# badge.net
KiCad netlist of a schematic drawn in EAGLE
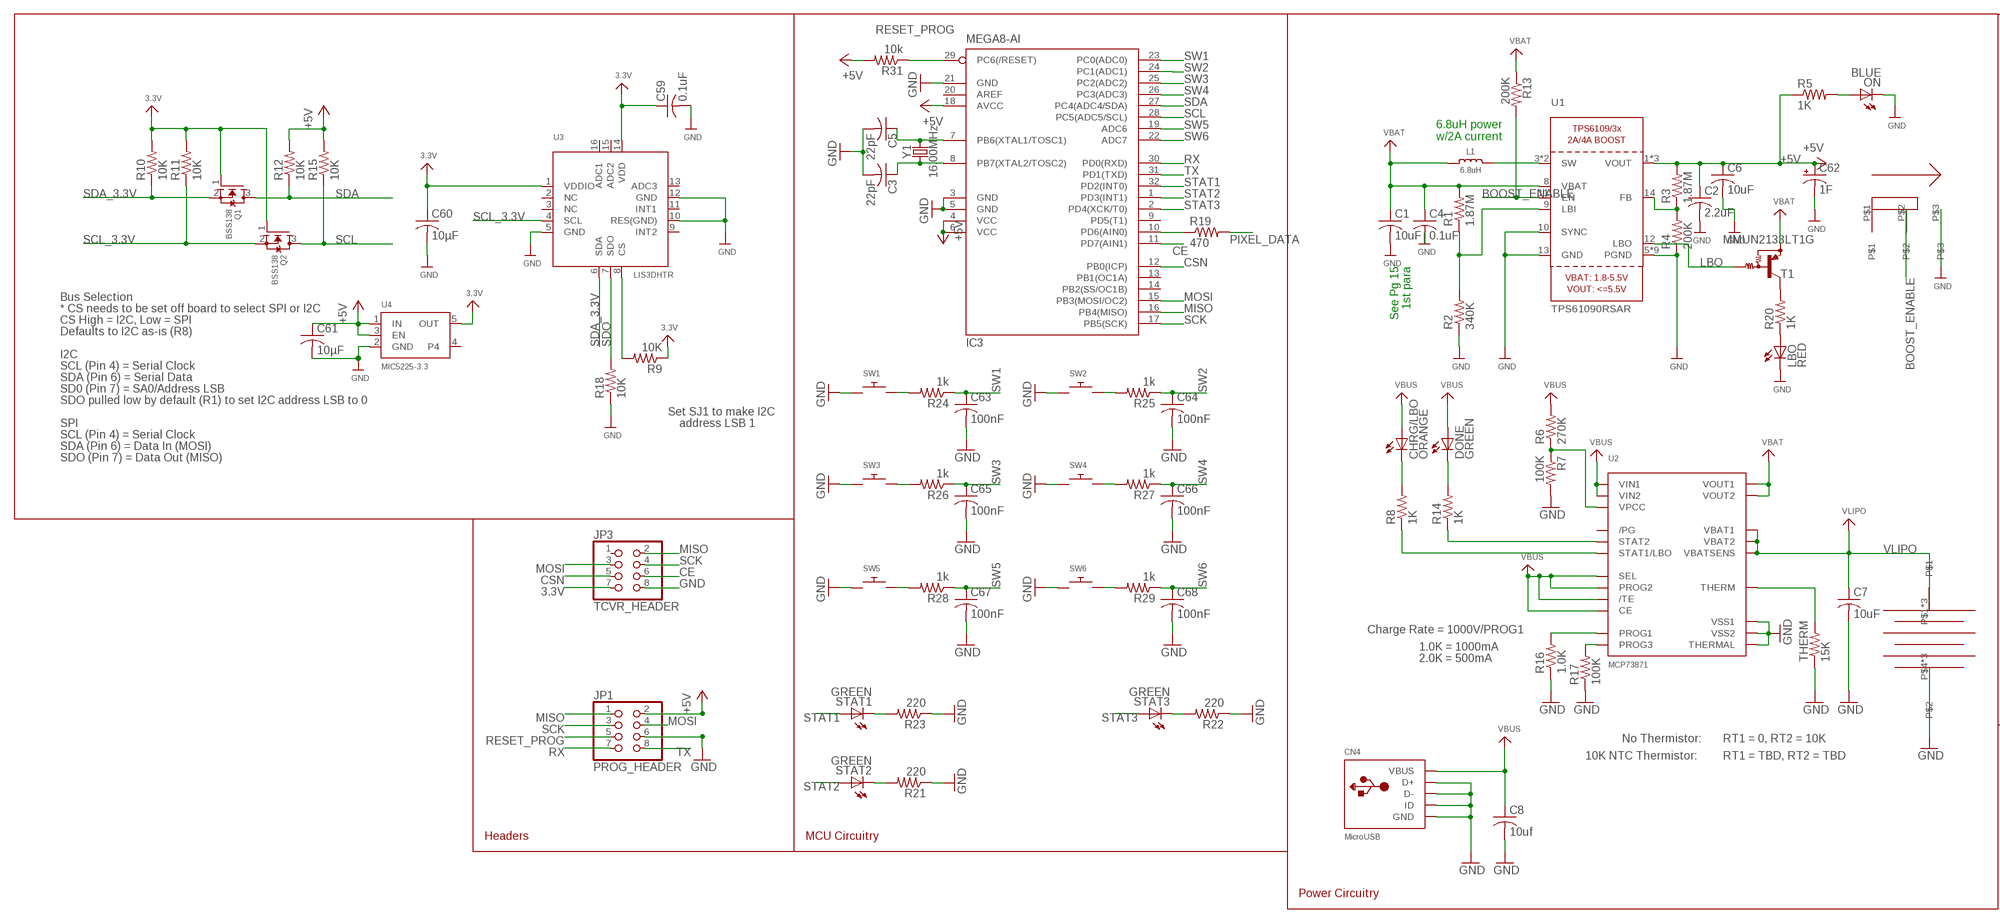
[diagram p0: schematic, sheet 1, part 1 of 2]
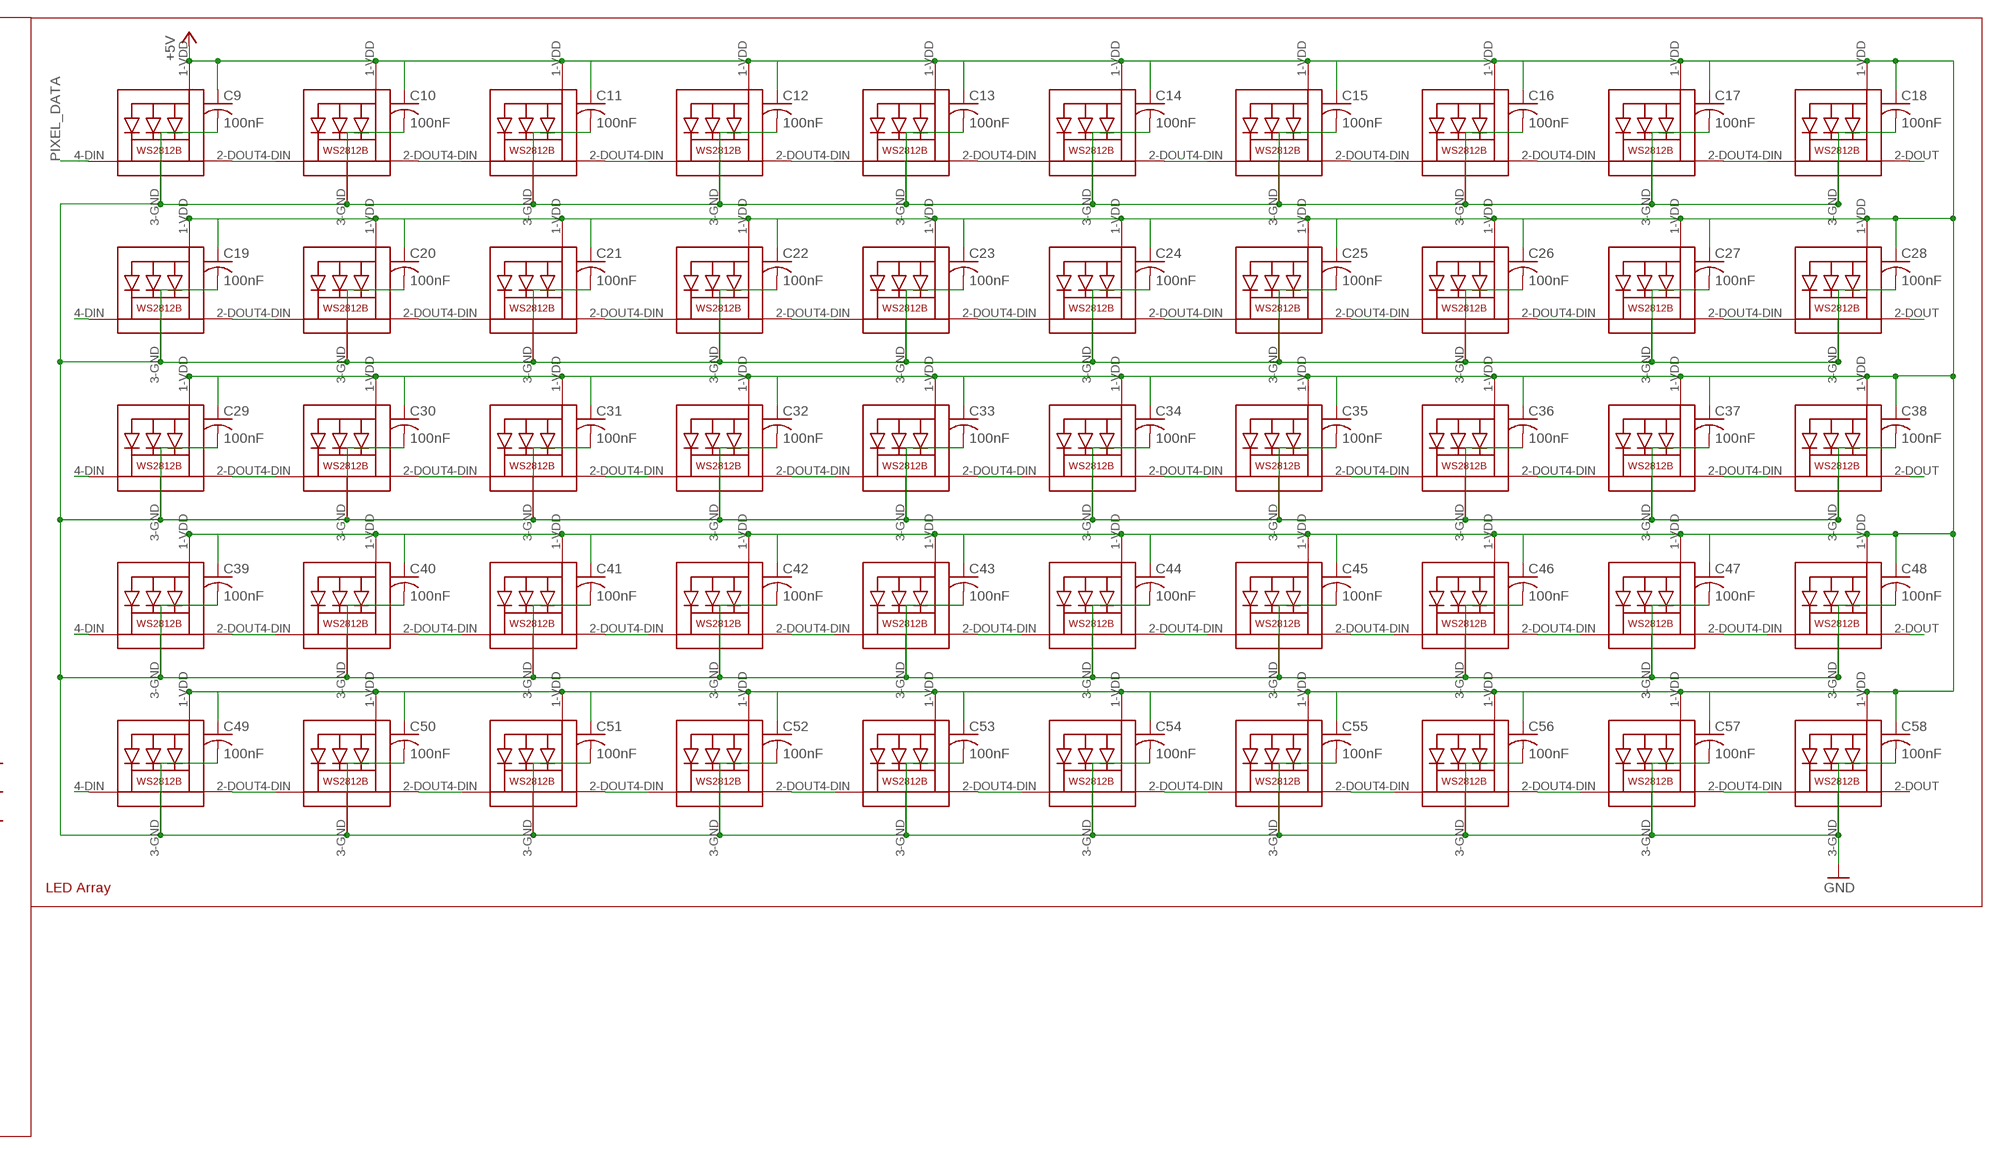
[diagram p1: schematic, sheet 1, part 2 of 2]

(export (version "E")
  (design (tool "Eeschema 10.0.6"))
  (components
    (comp (ref "C1")
      (value "10uF")
      (footprint "eagle-import:C1210")
      (libsource (lib "eagle-import") (part "resistor_348_C-USC1210"))
    )
    (comp (ref "C2")
      (value "2.2uF")
      (footprint "eagle-import:C0805")
      (libsource (lib "eagle-import") (part "C-USC0805"))
    )
    (comp (ref "C3")
      (value "22pF")
      (footprint "eagle-import:C0603")
      (libsource (lib "eagle-import") (part "resistor_348_C-USC0603"))
    )
    (comp (ref "C4")
      (value "0.1uF")
      (footprint "eagle-import:C0805")
      (libsource (lib "eagle-import") (part "C-USC0805"))
    )
    (comp (ref "C5")
      (value "22pF")
      (footprint "eagle-import:C0603")
      (libsource (lib "eagle-import") (part "resistor_348_C-USC0603"))
    )
    (comp (ref "C6")
      (value "10uF")
      (footprint "eagle-import:C1210")
      (libsource (lib "eagle-import") (part "resistor_348_C-USC1210"))
    )
    (comp (ref "C7")
      (value "10uF")
      (footprint "eagle-import:C1210")
      (libsource (lib "eagle-import") (part "resistor_348_C-USC1210"))
    )
    (comp (ref "C8")
      (value "10uf")
      (footprint "eagle-import:C0805")
      (libsource (lib "eagle-import") (part "C-USC0805"))
    )
    (comp (ref "C9")
      (value "100nF")
      (footprint "eagle-import:C0603")
      (libsource (lib "eagle-import") (part "resistor_348_C-USC0603"))
    )
    (comp (ref "C10")
      (value "100nF")
      (footprint "eagle-import:C0603")
      (libsource (lib "eagle-import") (part "resistor_348_C-USC0603"))
    )
    (comp (ref "C11")
      (value "100nF")
      (footprint "eagle-import:C0603")
      (libsource (lib "eagle-import") (part "resistor_348_C-USC0603"))
    )
    (comp (ref "C12")
      (value "100nF")
      (footprint "eagle-import:C0603")
      (libsource (lib "eagle-import") (part "resistor_348_C-USC0603"))
    )
    (comp (ref "C13")
      (value "100nF")
      (footprint "eagle-import:C0603")
      (libsource (lib "eagle-import") (part "resistor_348_C-USC0603"))
    )
    (comp (ref "C14")
      (value "100nF")
      (footprint "eagle-import:C0603")
      (libsource (lib "eagle-import") (part "resistor_348_C-USC0603"))
    )
    (comp (ref "C15")
      (value "100nF")
      (footprint "eagle-import:C0603")
      (libsource (lib "eagle-import") (part "resistor_348_C-USC0603"))
    )
    (comp (ref "C16")
      (value "100nF")
      (footprint "eagle-import:C0603")
      (libsource (lib "eagle-import") (part "resistor_348_C-USC0603"))
    )
    (comp (ref "C17")
      (value "100nF")
      (footprint "eagle-import:C0603")
      (libsource (lib "eagle-import") (part "resistor_348_C-USC0603"))
    )
    (comp (ref "C18")
      (value "100nF")
      (footprint "eagle-import:C0603")
      (libsource (lib "eagle-import") (part "resistor_348_C-USC0603"))
    )
    (comp (ref "C19")
      (value "100nF")
      (footprint "eagle-import:C0603")
      (libsource (lib "eagle-import") (part "resistor_348_C-USC0603"))
    )
    (comp (ref "C20")
      (value "100nF")
      (footprint "eagle-import:C0603")
      (libsource (lib "eagle-import") (part "resistor_348_C-USC0603"))
    )
    (comp (ref "C21")
      (value "100nF")
      (footprint "eagle-import:C0603")
      (libsource (lib "eagle-import") (part "resistor_348_C-USC0603"))
    )
    (comp (ref "C22")
      (value "100nF")
      (footprint "eagle-import:C0603")
      (libsource (lib "eagle-import") (part "resistor_348_C-USC0603"))
    )
    (comp (ref "C23")
      (value "100nF")
      (footprint "eagle-import:C0603")
      (libsource (lib "eagle-import") (part "resistor_348_C-USC0603"))
    )
    (comp (ref "C24")
      (value "100nF")
      (footprint "eagle-import:C0603")
      (libsource (lib "eagle-import") (part "resistor_348_C-USC0603"))
    )
    (comp (ref "C25")
      (value "100nF")
      (footprint "eagle-import:C0603")
      (libsource (lib "eagle-import") (part "resistor_348_C-USC0603"))
    )
    (comp (ref "C26")
      (value "100nF")
      (footprint "eagle-import:C0603")
      (libsource (lib "eagle-import") (part "resistor_348_C-USC0603"))
    )
    (comp (ref "C27")
      (value "100nF")
      (footprint "eagle-import:C0603")
      (libsource (lib "eagle-import") (part "resistor_348_C-USC0603"))
    )
    (comp (ref "C28")
      (value "100nF")
      (footprint "eagle-import:C0603")
      (libsource (lib "eagle-import") (part "resistor_348_C-USC0603"))
    )
    (comp (ref "C29")
      (value "100nF")
      (footprint "eagle-import:C0603")
      (libsource (lib "eagle-import") (part "resistor_348_C-USC0603"))
    )
    (comp (ref "C30")
      (value "100nF")
      (footprint "eagle-import:C0603")
      (libsource (lib "eagle-import") (part "resistor_348_C-USC0603"))
    )
    (comp (ref "C31")
      (value "100nF")
      (footprint "eagle-import:C0603")
      (libsource (lib "eagle-import") (part "resistor_348_C-USC0603"))
    )
    (comp (ref "C32")
      (value "100nF")
      (footprint "eagle-import:C0603")
      (libsource (lib "eagle-import") (part "resistor_348_C-USC0603"))
    )
    (comp (ref "C33")
      (value "100nF")
      (footprint "eagle-import:C0603")
      (libsource (lib "eagle-import") (part "resistor_348_C-USC0603"))
    )
    (comp (ref "C34")
      (value "100nF")
      (footprint "eagle-import:C0603")
      (libsource (lib "eagle-import") (part "resistor_348_C-USC0603"))
    )
    (comp (ref "C35")
      (value "100nF")
      (footprint "eagle-import:C0603")
      (libsource (lib "eagle-import") (part "resistor_348_C-USC0603"))
    )
    (comp (ref "C36")
      (value "100nF")
      (footprint "eagle-import:C0603")
      (libsource (lib "eagle-import") (part "resistor_348_C-USC0603"))
    )
    (comp (ref "C37")
      (value "100nF")
      (footprint "eagle-import:C0603")
      (libsource (lib "eagle-import") (part "resistor_348_C-USC0603"))
    )
    (comp (ref "C38")
      (value "100nF")
      (footprint "eagle-import:C0603")
      (libsource (lib "eagle-import") (part "resistor_348_C-USC0603"))
    )
    (comp (ref "C39")
      (value "100nF")
      (footprint "eagle-import:C0603")
      (libsource (lib "eagle-import") (part "resistor_348_C-USC0603"))
    )
    (comp (ref "C40")
      (value "100nF")
      (footprint "eagle-import:C0603")
      (libsource (lib "eagle-import") (part "resistor_348_C-USC0603"))
    )
    (comp (ref "C41")
      (value "100nF")
      (footprint "eagle-import:C0603")
      (libsource (lib "eagle-import") (part "resistor_348_C-USC0603"))
    )
    (comp (ref "C42")
      (value "100nF")
      (footprint "eagle-import:C0603")
      (libsource (lib "eagle-import") (part "resistor_348_C-USC0603"))
    )
    (comp (ref "C43")
      (value "100nF")
      (footprint "eagle-import:C0603")
      (libsource (lib "eagle-import") (part "resistor_348_C-USC0603"))
    )
    (comp (ref "C44")
      (value "100nF")
      (footprint "eagle-import:C0603")
      (libsource (lib "eagle-import") (part "resistor_348_C-USC0603"))
    )
    (comp (ref "C45")
      (value "100nF")
      (footprint "eagle-import:C0603")
      (libsource (lib "eagle-import") (part "resistor_348_C-USC0603"))
    )
    (comp (ref "C46")
      (value "100nF")
      (footprint "eagle-import:C0603")
      (libsource (lib "eagle-import") (part "resistor_348_C-USC0603"))
    )
    (comp (ref "C47")
      (value "100nF")
      (footprint "eagle-import:C0603")
      (libsource (lib "eagle-import") (part "resistor_348_C-USC0603"))
    )
    (comp (ref "C48")
      (value "100nF")
      (footprint "eagle-import:C0603")
      (libsource (lib "eagle-import") (part "resistor_348_C-USC0603"))
    )
    (comp (ref "C49")
      (value "100nF")
      (footprint "eagle-import:C0603")
      (libsource (lib "eagle-import") (part "resistor_348_C-USC0603"))
    )
    (comp (ref "C50")
      (value "100nF")
      (footprint "eagle-import:C0603")
      (libsource (lib "eagle-import") (part "resistor_348_C-USC0603"))
    )
    (comp (ref "C51")
      (value "100nF")
      (footprint "eagle-import:C0603")
      (libsource (lib "eagle-import") (part "resistor_348_C-USC0603"))
    )
    (comp (ref "C52")
      (value "100nF")
      (footprint "eagle-import:C0603")
      (libsource (lib "eagle-import") (part "resistor_348_C-USC0603"))
    )
    (comp (ref "C53")
      (value "100nF")
      (footprint "eagle-import:C0603")
      (libsource (lib "eagle-import") (part "resistor_348_C-USC0603"))
    )
    (comp (ref "C54")
      (value "100nF")
      (footprint "eagle-import:C0603")
      (libsource (lib "eagle-import") (part "resistor_348_C-USC0603"))
    )
    (comp (ref "C55")
      (value "100nF")
      (footprint "eagle-import:C0603")
      (libsource (lib "eagle-import") (part "resistor_348_C-USC0603"))
    )
    (comp (ref "C56")
      (value "100nF")
      (footprint "eagle-import:C0603")
      (libsource (lib "eagle-import") (part "resistor_348_C-USC0603"))
    )
    (comp (ref "C57")
      (value "100nF")
      (footprint "eagle-import:C0603")
      (libsource (lib "eagle-import") (part "resistor_348_C-USC0603"))
    )
    (comp (ref "C58")
      (value "100nF")
      (footprint "eagle-import:C0603")
      (libsource (lib "eagle-import") (part "resistor_348_C-USC0603"))
    )
    (comp (ref "C59")
      (value "0.1uF")
      (footprint "eagle-import:C0603")
      (libsource (lib "eagle-import") (part "resistor_348_C-USC0603"))
    )
    (comp (ref "C60")
      (value "10µF")
      (footprint "eagle-import:C0805")
      (libsource (lib "eagle-import") (part "resistor_348_C-USC0805"))
    )
    (comp (ref "C61")
      (value "10µF")
      (footprint "eagle-import:C0805")
      (libsource (lib "eagle-import") (part "resistor_348_C-USC0805"))
    )
    (comp (ref "C62")
      (value "1F")
      (footprint "eagle-import:E5-8,5")
      (libsource (lib "eagle-import") (part "CPOL-USE5-8.5"))
    )
    (comp (ref "C63")
      (value "100nF")
      (footprint "eagle-import:C0603")
      (libsource (lib "eagle-import") (part "resistor_348_C-USC0603"))
    )
    (comp (ref "C64")
      (value "100nF")
      (footprint "eagle-import:C0603")
      (libsource (lib "eagle-import") (part "resistor_348_C-USC0603"))
    )
    (comp (ref "C65")
      (value "100nF")
      (footprint "eagle-import:C0603")
      (libsource (lib "eagle-import") (part "resistor_348_C-USC0603"))
    )
    (comp (ref "C66")
      (value "100nF")
      (footprint "eagle-import:C0603")
      (libsource (lib "eagle-import") (part "resistor_348_C-USC0603"))
    )
    (comp (ref "C67")
      (value "100nF")
      (footprint "eagle-import:C0603")
      (libsource (lib "eagle-import") (part "resistor_348_C-USC0603"))
    )
    (comp (ref "C68")
      (value "100nF")
      (footprint "eagle-import:C0603")
      (libsource (lib "eagle-import") (part "resistor_348_C-USC0603"))
    )
    (comp (ref "CHRG/LBO")
      (value "ORANGE")
      (footprint "eagle-import:ADAFRUIT_CHIPLED_0603")
      (libsource (lib "eagle-import") (part "ADAFRUIT_LEDCHIPLED_0603"))
    )
    (comp (ref "CN4")
      (value "MicroUSB")
      (footprint "eagle-import:4UCONN_20329")
      (libsource (lib "eagle-import") (part "USBMICRO_20329"))
    )
    (comp (ref "DONE")
      (value "GREEN")
      (footprint "eagle-import:ADAFRUIT_CHIPLED_0603")
      (libsource (lib "eagle-import") (part "ADAFRUIT_LEDCHIPLED_0603"))
    )
    (comp (ref "IC3")
      (value "MEGA8-AI")
      (footprint "eagle-import:TQFP32-08")
      (fields (field (name "MPN") "ATMEGA8-16AU"))
      (libsource (lib "eagle-import") (part "MEGA8-AI"))
    )
    (comp (ref "JP1")
      (value "PROG_HEADER")
      (footprint "eagle-import:2X04")
      (libsource (lib "eagle-import") (part "PINHD-2X4"))
    )
    (comp (ref "JP3")
      (value "TCVR_HEADER")
      (footprint "eagle-import:2X04")
      (libsource (lib "eagle-import") (part "PINHD-2X4"))
    )
    (comp (ref "L1")
      (value "6.8uH")
      (footprint "eagle-import:INDUCTOR_5X5MM_TDK_VLC5045")
      (libsource (lib "eagle-import") (part "INDUCTORTDK_VLC5045"))
    )
    (comp (ref "LBO")
      (value "RED")
      (footprint "eagle-import:ADAFRUIT_CHIPLED_0603")
      (libsource (lib "eagle-import") (part "ADAFRUIT_LEDCHIPLED_0603"))
    )
    (comp (ref "LED1")
      (value "WS2812B5050-NARROW")
      (footprint "eagle-import:WS2812B-NARROW")
      (libsource (lib "eagle-import") (part "WS2812B5050-NARROW"))
    )
    (comp (ref "LED2")
      (value "WS2812B5050-NARROW")
      (footprint "eagle-import:WS2812B-NARROW")
      (libsource (lib "eagle-import") (part "WS2812B5050-NARROW"))
    )
    (comp (ref "LED3")
      (value "WS2812B5050-NARROW")
      (footprint "eagle-import:WS2812B-NARROW")
      (libsource (lib "eagle-import") (part "WS2812B5050-NARROW"))
    )
    (comp (ref "LED4")
      (value "WS2812B5050-NARROW")
      (footprint "eagle-import:WS2812B-NARROW")
      (libsource (lib "eagle-import") (part "WS2812B5050-NARROW"))
    )
    (comp (ref "LED5")
      (value "WS2812B5050-NARROW")
      (footprint "eagle-import:WS2812B-NARROW")
      (libsource (lib "eagle-import") (part "WS2812B5050-NARROW"))
    )
    (comp (ref "LED6")
      (value "WS2812B5050-NARROW")
      (footprint "eagle-import:WS2812B-NARROW")
      (libsource (lib "eagle-import") (part "WS2812B5050-NARROW"))
    )
    (comp (ref "LED7")
      (value "WS2812B5050-NARROW")
      (footprint "eagle-import:WS2812B-NARROW")
      (libsource (lib "eagle-import") (part "WS2812B5050-NARROW"))
    )
    (comp (ref "LED8")
      (value "WS2812B5050-NARROW")
      (footprint "eagle-import:WS2812B-NARROW")
      (libsource (lib "eagle-import") (part "WS2812B5050-NARROW"))
    )
    (comp (ref "LED9")
      (value "WS2812B5050-NARROW")
      (footprint "eagle-import:WS2812B-NARROW")
      (libsource (lib "eagle-import") (part "WS2812B5050-NARROW"))
    )
    (comp (ref "LED10")
      (value "WS2812B5050-NARROW")
      (footprint "eagle-import:WS2812B-NARROW")
      (libsource (lib "eagle-import") (part "WS2812B5050-NARROW"))
    )
    (comp (ref "LED11")
      (value "WS2812B5050-NARROW")
      (footprint "eagle-import:WS2812B-NARROW")
      (libsource (lib "eagle-import") (part "WS2812B5050-NARROW"))
    )
    (comp (ref "LED12")
      (value "WS2812B5050-NARROW")
      (footprint "eagle-import:WS2812B-NARROW")
      (libsource (lib "eagle-import") (part "WS2812B5050-NARROW"))
    )
    (comp (ref "LED13")
      (value "WS2812B5050-NARROW")
      (footprint "eagle-import:WS2812B-NARROW")
      (libsource (lib "eagle-import") (part "WS2812B5050-NARROW"))
    )
    (comp (ref "LED14")
      (value "WS2812B5050-NARROW")
      (footprint "eagle-import:WS2812B-NARROW")
      (libsource (lib "eagle-import") (part "WS2812B5050-NARROW"))
    )
    (comp (ref "LED15")
      (value "WS2812B5050-NARROW")
      (footprint "eagle-import:WS2812B-NARROW")
      (libsource (lib "eagle-import") (part "WS2812B5050-NARROW"))
    )
    (comp (ref "LED16")
      (value "WS2812B5050-NARROW")
      (footprint "eagle-import:WS2812B-NARROW")
      (libsource (lib "eagle-import") (part "WS2812B5050-NARROW"))
    )
    (comp (ref "LED17")
      (value "WS2812B5050-NARROW")
      (footprint "eagle-import:WS2812B-NARROW")
      (libsource (lib "eagle-import") (part "WS2812B5050-NARROW"))
    )
    (comp (ref "LED18")
      (value "WS2812B5050-NARROW")
      (footprint "eagle-import:WS2812B-NARROW")
      (libsource (lib "eagle-import") (part "WS2812B5050-NARROW"))
    )
    (comp (ref "LED19")
      (value "WS2812B5050-NARROW")
      (footprint "eagle-import:WS2812B-NARROW")
      (libsource (lib "eagle-import") (part "WS2812B5050-NARROW"))
    )
    (comp (ref "LED20")
      (value "WS2812B5050-NARROW")
      (footprint "eagle-import:WS2812B-NARROW")
      (libsource (lib "eagle-import") (part "WS2812B5050-NARROW"))
    )
    (comp (ref "LED21")
      (value "WS2812B5050-NARROW")
      (footprint "eagle-import:WS2812B-NARROW")
      (libsource (lib "eagle-import") (part "WS2812B5050-NARROW"))
    )
    (comp (ref "LED22")
      (value "WS2812B5050-NARROW")
      (footprint "eagle-import:WS2812B-NARROW")
      (libsource (lib "eagle-import") (part "WS2812B5050-NARROW"))
    )
    (comp (ref "LED23")
      (value "WS2812B5050-NARROW")
      (footprint "eagle-import:WS2812B-NARROW")
      (libsource (lib "eagle-import") (part "WS2812B5050-NARROW"))
    )
    (comp (ref "LED24")
      (value "WS2812B5050-NARROW")
      (footprint "eagle-import:WS2812B-NARROW")
      (libsource (lib "eagle-import") (part "WS2812B5050-NARROW"))
    )
    (comp (ref "LED25")
      (value "WS2812B5050-NARROW")
      (footprint "eagle-import:WS2812B-NARROW")
      (libsource (lib "eagle-import") (part "WS2812B5050-NARROW"))
    )
    (comp (ref "LED26")
      (value "WS2812B5050-NARROW")
      (footprint "eagle-import:WS2812B-NARROW")
      (libsource (lib "eagle-import") (part "WS2812B5050-NARROW"))
    )
    (comp (ref "LED27")
      (value "WS2812B5050-NARROW")
      (footprint "eagle-import:WS2812B-NARROW")
      (libsource (lib "eagle-import") (part "WS2812B5050-NARROW"))
    )
    (comp (ref "LED28")
      (value "WS2812B5050-NARROW")
      (footprint "eagle-import:WS2812B-NARROW")
      (libsource (lib "eagle-import") (part "WS2812B5050-NARROW"))
    )
    (comp (ref "LED29")
      (value "WS2812B5050-NARROW")
      (footprint "eagle-import:WS2812B-NARROW")
      (libsource (lib "eagle-import") (part "WS2812B5050-NARROW"))
    )
    (comp (ref "LED30")
      (value "WS2812B5050-NARROW")
      (footprint "eagle-import:WS2812B-NARROW")
      (libsource (lib "eagle-import") (part "WS2812B5050-NARROW"))
    )
    (comp (ref "LED31")
      (value "WS2812B5050-NARROW")
      (footprint "eagle-import:WS2812B-NARROW")
      (libsource (lib "eagle-import") (part "WS2812B5050-NARROW"))
    )
    (comp (ref "LED32")
      (value "WS2812B5050-NARROW")
      (footprint "eagle-import:WS2812B-NARROW")
      (libsource (lib "eagle-import") (part "WS2812B5050-NARROW"))
    )
    (comp (ref "LED33")
      (value "WS2812B5050-NARROW")
      (footprint "eagle-import:WS2812B-NARROW")
      (libsource (lib "eagle-import") (part "WS2812B5050-NARROW"))
    )
    (comp (ref "LED34")
      (value "WS2812B5050-NARROW")
      (footprint "eagle-import:WS2812B-NARROW")
      (libsource (lib "eagle-import") (part "WS2812B5050-NARROW"))
    )
    (comp (ref "LED35")
      (value "WS2812B5050-NARROW")
      (footprint "eagle-import:WS2812B-NARROW")
      (libsource (lib "eagle-import") (part "WS2812B5050-NARROW"))
    )
    (comp (ref "LED36")
      (value "WS2812B5050-NARROW")
      (footprint "eagle-import:WS2812B-NARROW")
      (libsource (lib "eagle-import") (part "WS2812B5050-NARROW"))
    )
    (comp (ref "LED37")
      (value "WS2812B5050-NARROW")
      (footprint "eagle-import:WS2812B-NARROW")
      (libsource (lib "eagle-import") (part "WS2812B5050-NARROW"))
    )
    (comp (ref "LED38")
      (value "WS2812B5050-NARROW")
      (footprint "eagle-import:WS2812B-NARROW")
      (libsource (lib "eagle-import") (part "WS2812B5050-NARROW"))
    )
    (comp (ref "LED39")
      (value "WS2812B5050-NARROW")
      (footprint "eagle-import:WS2812B-NARROW")
      (libsource (lib "eagle-import") (part "WS2812B5050-NARROW"))
    )
    (comp (ref "LED40")
      (value "WS2812B5050-NARROW")
      (footprint "eagle-import:WS2812B-NARROW")
      (libsource (lib "eagle-import") (part "WS2812B5050-NARROW"))
    )
    (comp (ref "LED41")
      (value "WS2812B5050-NARROW")
      (footprint "eagle-import:WS2812B-NARROW")
      (libsource (lib "eagle-import") (part "WS2812B5050-NARROW"))
    )
    (comp (ref "LED42")
      (value "WS2812B5050-NARROW")
      (footprint "eagle-import:WS2812B-NARROW")
      (libsource (lib "eagle-import") (part "WS2812B5050-NARROW"))
    )
    (comp (ref "LED43")
      (value "WS2812B5050-NARROW")
      (footprint "eagle-import:WS2812B-NARROW")
      (libsource (lib "eagle-import") (part "WS2812B5050-NARROW"))
    )
    (comp (ref "LED44")
      (value "WS2812B5050-NARROW")
      (footprint "eagle-import:WS2812B-NARROW")
      (libsource (lib "eagle-import") (part "WS2812B5050-NARROW"))
    )
    (comp (ref "LED45")
      (value "WS2812B5050-NARROW")
      (footprint "eagle-import:WS2812B-NARROW")
      (libsource (lib "eagle-import") (part "WS2812B5050-NARROW"))
    )
    (comp (ref "LED46")
      (value "WS2812B5050-NARROW")
      (footprint "eagle-import:WS2812B-NARROW")
      (libsource (lib "eagle-import") (part "WS2812B5050-NARROW"))
    )
    (comp (ref "LED47")
      (value "WS2812B5050-NARROW")
      (footprint "eagle-import:WS2812B-NARROW")
      (libsource (lib "eagle-import") (part "WS2812B5050-NARROW"))
    )
    (comp (ref "LED48")
      (value "WS2812B5050-NARROW")
      (footprint "eagle-import:WS2812B-NARROW")
      (libsource (lib "eagle-import") (part "WS2812B5050-NARROW"))
    )
    (comp (ref "LED49")
      (value "WS2812B5050-NARROW")
      (footprint "eagle-import:WS2812B-NARROW")
      (libsource (lib "eagle-import") (part "WS2812B5050-NARROW"))
    )
    (comp (ref "LED50")
      (value "WS2812B5050-NARROW")
      (footprint "eagle-import:WS2812B-NARROW")
      (libsource (lib "eagle-import") (part "WS2812B5050-NARROW"))
    )
    (comp (ref "ON")
      (value "BLUE")
      (footprint "eagle-import:ADAFRUIT_CHIPLED_0603")
      (libsource (lib "eagle-import") (part "ADAFRUIT_LEDCHIPLED_0603"))
    )
    (comp (ref "Q1")
      (value "BSS138")
      (footprint "eagle-import:SOT23-WIDE")
      (libsource (lib "eagle-import") (part "MOSFET-NWIDE"))
    )
    (comp (ref "Q2")
      (value "BSS138")
      (footprint "eagle-import:SOT23-WIDE")
      (libsource (lib "eagle-import") (part "MOSFET-NWIDE"))
    )
    (comp (ref "R1")
      (value "1.87M")
      (footprint "eagle-import:R0805")
      (libsource (lib "eagle-import") (part "R-US_R0805"))
    )
    (comp (ref "R2")
      (value "340K")
      (footprint "eagle-import:R0805")
      (libsource (lib "eagle-import") (part "R-US_R0805"))
    )
    (comp (ref "R3")
      (value "1.87M")
      (footprint "eagle-import:R0805")
      (libsource (lib "eagle-import") (part "R-US_R0805"))
    )
    (comp (ref "R4")
      (value "200K")
      (footprint "eagle-import:R0805")
      (libsource (lib "eagle-import") (part "R-US_R0805"))
    )
    (comp (ref "R5")
      (value "1K")
      (footprint "eagle-import:R0805")
      (libsource (lib "eagle-import") (part "R-US_R0805"))
    )
    (comp (ref "R6")
      (value "270K")
      (footprint "eagle-import:R0805")
      (libsource (lib "eagle-import") (part "R-US_R0805"))
    )
    (comp (ref "R7")
      (value "100K")
      (footprint "eagle-import:R0805")
      (libsource (lib "eagle-import") (part "R-US_R0805"))
    )
    (comp (ref "R8")
      (value "1K")
      (footprint "eagle-import:R0805")
      (libsource (lib "eagle-import") (part "R-US_R0805"))
    )
    (comp (ref "R9")
      (value "10K")
      (footprint "eagle-import:R0603")
      (libsource (lib "eagle-import") (part "resistor_348_R-US_R0603"))
    )
    (comp (ref "R10")
      (value "10K")
      (footprint "eagle-import:R0603")
      (libsource (lib "eagle-import") (part "resistor_348_R-US_R0603"))
    )
    (comp (ref "R11")
      (value "10K")
      (footprint "eagle-import:R0603")
      (libsource (lib "eagle-import") (part "resistor_348_R-US_R0603"))
    )
    (comp (ref "R12")
      (value "10K")
      (footprint "eagle-import:R0603")
      (libsource (lib "eagle-import") (part "resistor_348_R-US_R0603"))
    )
    (comp (ref "R13")
      (value "200K")
      (footprint "eagle-import:R0805")
      (libsource (lib "eagle-import") (part "R-US_R0805"))
    )
    (comp (ref "R14")
      (value "1K")
      (footprint "eagle-import:R0805")
      (libsource (lib "eagle-import") (part "R-US_R0805"))
    )
    (comp (ref "R15")
      (value "10K")
      (footprint "eagle-import:R0603")
      (libsource (lib "eagle-import") (part "resistor_348_R-US_R0603"))
    )
    (comp (ref "R16")
      (value "1.0K")
      (footprint "eagle-import:R0805")
      (libsource (lib "eagle-import") (part "R-US_R0805"))
    )
    (comp (ref "R17")
      (value "100K")
      (footprint "eagle-import:R0805")
      (libsource (lib "eagle-import") (part "R-US_R0805"))
    )
    (comp (ref "R18")
      (value "10K")
      (footprint "eagle-import:R0603")
      (libsource (lib "eagle-import") (part "resistor_348_R-US_R0603"))
    )
    (comp (ref "R19")
      (value "470")
      (footprint "eagle-import:R0805")
      (libsource (lib "eagle-import") (part "resistor_348_R-US_R0805"))
    )
    (comp (ref "R20")
      (value "1K")
      (footprint "eagle-import:R0805")
      (libsource (lib "eagle-import") (part "R-US_R0805"))
    )
    (comp (ref "R21")
      (value "220")
      (footprint "eagle-import:M0805")
      (libsource (lib "eagle-import") (part "resistor_348_R-US_M0805"))
    )
    (comp (ref "R22")
      (value "220")
      (footprint "eagle-import:M0805")
      (libsource (lib "eagle-import") (part "resistor_348_R-US_M0805"))
    )
    (comp (ref "R23")
      (value "220")
      (footprint "eagle-import:M0805")
      (libsource (lib "eagle-import") (part "resistor_348_R-US_M0805"))
    )
    (comp (ref "R24")
      (value "1k")
      (footprint "eagle-import:R0603")
      (libsource (lib "eagle-import") (part "resistor_348_R-US_R0603"))
    )
    (comp (ref "R25")
      (value "1k")
      (footprint "eagle-import:R0603")
      (libsource (lib "eagle-import") (part "resistor_348_R-US_R0603"))
    )
    (comp (ref "R26")
      (value "1k")
      (footprint "eagle-import:R0603")
      (libsource (lib "eagle-import") (part "resistor_348_R-US_R0603"))
    )
    (comp (ref "R27")
      (value "1k")
      (footprint "eagle-import:R0603")
      (libsource (lib "eagle-import") (part "resistor_348_R-US_R0603"))
    )
    (comp (ref "R28")
      (value "1k")
      (footprint "eagle-import:R0603")
      (libsource (lib "eagle-import") (part "resistor_348_R-US_R0603"))
    )
    (comp (ref "R29")
      (value "1k")
      (footprint "eagle-import:R0603")
      (libsource (lib "eagle-import") (part "resistor_348_R-US_R0603"))
    )
    (comp (ref "R31")
      (value "10k")
      (footprint "eagle-import:M0805")
      (libsource (lib "eagle-import") (part "rcl_334_R-US_M0805"))
    )
    (comp (ref "STAT1")
      (value "GREEN")
      (footprint "eagle-import:ADAFRUIT_CHIPLED_0603")
      (libsource (lib "eagle-import") (part "ADAFRUIT_LEDCHIPLED_0603"))
    )
    (comp (ref "STAT2")
      (value "GREEN")
      (footprint "eagle-import:ADAFRUIT_CHIPLED_0603")
      (libsource (lib "eagle-import") (part "ADAFRUIT_LEDCHIPLED_0603"))
    )
    (comp (ref "STAT3")
      (value "GREEN")
      (footprint "eagle-import:ADAFRUIT_CHIPLED_0603")
      (libsource (lib "eagle-import") (part "ADAFRUIT_LEDCHIPLED_0603"))
    )
    (comp (ref "SW1")
      (value "SWITCH_PUSHBUTTONEVQ-PE")
      (footprint "eagle-import:TACT_PANA-EVQ")
      (libsource (lib "eagle-import") (part "SWITCH_PUSHBUTTONEVQ-PE"))
    )
    (comp (ref "SW2")
      (value "SWITCH_PUSHBUTTONEVQ-PE")
      (footprint "eagle-import:TACT_PANA-EVQ")
      (libsource (lib "eagle-import") (part "SWITCH_PUSHBUTTONEVQ-PE"))
    )
    (comp (ref "SW3")
      (value "SWITCH_PUSHBUTTONEVQ-PE")
      (footprint "eagle-import:TACT_PANA-EVQ")
      (libsource (lib "eagle-import") (part "SWITCH_PUSHBUTTONEVQ-PE"))
    )
    (comp (ref "SW4")
      (value "SWITCH_PUSHBUTTONEVQ-PE")
      (footprint "eagle-import:TACT_PANA-EVQ")
      (libsource (lib "eagle-import") (part "SWITCH_PUSHBUTTONEVQ-PE"))
    )
    (comp (ref "SW5")
      (value "SWITCH_PUSHBUTTONEVQ-PE")
      (footprint "eagle-import:TACT_PANA-EVQ")
      (libsource (lib "eagle-import") (part "SWITCH_PUSHBUTTONEVQ-PE"))
    )
    (comp (ref "SW6")
      (value "SWITCH_PUSHBUTTONEVQ-PE")
      (footprint "eagle-import:TACT_PANA-EVQ")
      (libsource (lib "eagle-import") (part "SWITCH_PUSHBUTTONEVQ-PE"))
    )
    (comp (ref "T1")
      (value "MMUN2133LT1G")
      (footprint "eagle-import:TRANSISTOR_SC59-BEC")
      (libsource (lib "eagle-import") (part "TRANSISTOR_-PNP_DRIVER-SC59-BECMUN2113T1"))
    )
    (comp (ref "THERM")
      (value "15K")
      (footprint "eagle-import:R0805")
      (libsource (lib "eagle-import") (part "R-US_R0805"))
    )
    (comp (ref "U$17")
      (value "CL-SB-12A-02T")
      (footprint "eagle-import:CL-SB-12A-02T")
      (libsource (lib "eagle-import") (part "CL-SB-12A-02T"))
    )
    (comp (ref "U$22")
      (value "54_BATTERY_CLIP")
      (footprint "eagle-import:54_BATTERY_CLIP")
      (libsource (lib "eagle-import") (part "54_BATTERY_CLIP"))
    )
    (comp (ref "U1")
      (value "TPS61090RSAR")
      (footprint "eagle-import:PVQFN-16")
      (libsource (lib "eagle-import") (part "VREG_TPS6103X"))
    )
    (comp (ref "U2")
      (value "MCP73871")
      (footprint "eagle-import:QFN20_4MM")
      (libsource (lib "eagle-import") (part "MCP73871"))
    )
    (comp (ref "U3")
      (value "LIS3DHTR")
      (footprint "eagle-import:LGA16_3X3MM")
      (libsource (lib "eagle-import") (part "ACCEL_LIS3DHTR"))
    )
    (comp (ref "U4")
      (value "MIC5225-3.3")
      (footprint "eagle-import:SOT23-5")
      (libsource (lib "eagle-import") (part "VREG_SOT23-5"))
    )
    (comp (ref "Y1")
      (value "16.00MHz")
      (footprint "eagle-import:CRYSTAL-SMD-3.2X2.5MM")
      (libsource (lib "eagle-import") (part "CRYSTALSMD-3.2X2.5"))
    )
  )
  (nets
    (net (code "1") (name "+5V") (class "Default")
      (node (ref "C10") (pin "1") (pinfunction "1_1") (pintype "passive"))
      (node (ref "C11") (pin "1") (pinfunction "1_1") (pintype "passive"))
      (node (ref "C12") (pin "1") (pinfunction "1_1") (pintype "passive"))
      (node (ref "C13") (pin "1") (pinfunction "1_1") (pintype "passive"))
      (node (ref "C14") (pin "1") (pinfunction "1_1") (pintype "passive"))
      (node (ref "C15") (pin "1") (pinfunction "1_1") (pintype "passive"))
      (node (ref "C16") (pin "1") (pinfunction "1_1") (pintype "passive"))
      (node (ref "C17") (pin "1") (pinfunction "1_1") (pintype "passive"))
      (node (ref "C18") (pin "1") (pinfunction "1_1") (pintype "passive"))
      (node (ref "C19") (pin "1") (pinfunction "1_1") (pintype "passive"))
      (node (ref "C2") (pin "1") (pinfunction "1_1") (pintype "passive"))
      (node (ref "C20") (pin "1") (pinfunction "1_1") (pintype "passive"))
      (node (ref "C21") (pin "1") (pinfunction "1_1") (pintype "passive"))
      (node (ref "C22") (pin "1") (pinfunction "1_1") (pintype "passive"))
      (node (ref "C23") (pin "1") (pinfunction "1_1") (pintype "passive"))
      (node (ref "C24") (pin "1") (pinfunction "1_1") (pintype "passive"))
      (node (ref "C25") (pin "1") (pinfunction "1_1") (pintype "passive"))
      (node (ref "C26") (pin "1") (pinfunction "1_1") (pintype "passive"))
      (node (ref "C27") (pin "1") (pinfunction "1_1") (pintype "passive"))
      (node (ref "C28") (pin "1") (pinfunction "1_1") (pintype "passive"))
      (node (ref "C29") (pin "1") (pinfunction "1_1") (pintype "passive"))
      (node (ref "C30") (pin "1") (pinfunction "1_1") (pintype "passive"))
      (node (ref "C31") (pin "1") (pinfunction "1_1") (pintype "passive"))
      (node (ref "C32") (pin "1") (pinfunction "1_1") (pintype "passive"))
      (node (ref "C33") (pin "1") (pinfunction "1_1") (pintype "passive"))
      (node (ref "C34") (pin "1") (pinfunction "1_1") (pintype "passive"))
      (node (ref "C35") (pin "1") (pinfunction "1_1") (pintype "passive"))
      (node (ref "C36") (pin "1") (pinfunction "1_1") (pintype "passive"))
      (node (ref "C37") (pin "1") (pinfunction "1_1") (pintype "passive"))
      (node (ref "C38") (pin "1") (pinfunction "1_1") (pintype "passive"))
      (node (ref "C39") (pin "1") (pinfunction "1_1") (pintype "passive"))
      (node (ref "C40") (pin "1") (pinfunction "1_1") (pintype "passive"))
      (node (ref "C41") (pin "1") (pinfunction "1_1") (pintype "passive"))
      (node (ref "C42") (pin "1") (pinfunction "1_1") (pintype "passive"))
      (node (ref "C43") (pin "1") (pinfunction "1_1") (pintype "passive"))
      (node (ref "C44") (pin "1") (pinfunction "1_1") (pintype "passive"))
      (node (ref "C45") (pin "1") (pinfunction "1_1") (pintype "passive"))
      (node (ref "C46") (pin "1") (pinfunction "1_1") (pintype "passive"))
      (node (ref "C47") (pin "1") (pinfunction "1_1") (pintype "passive"))
      (node (ref "C48") (pin "1") (pinfunction "1_1") (pintype "passive"))
      (node (ref "C49") (pin "1") (pinfunction "1_1") (pintype "passive"))
      (node (ref "C50") (pin "1") (pinfunction "1_1") (pintype "passive"))
      (node (ref "C51") (pin "1") (pinfunction "1_1") (pintype "passive"))
      (node (ref "C52") (pin "1") (pinfunction "1_1") (pintype "passive"))
      (node (ref "C53") (pin "1") (pinfunction "1_1") (pintype "passive"))
      (node (ref "C54") (pin "1") (pinfunction "1_1") (pintype "passive"))
      (node (ref "C55") (pin "1") (pinfunction "1_1") (pintype "passive"))
      (node (ref "C56") (pin "1") (pinfunction "1_1") (pintype "passive"))
      (node (ref "C57") (pin "1") (pinfunction "1_1") (pintype "passive"))
      (node (ref "C58") (pin "1") (pinfunction "1_1") (pintype "passive"))
      (node (ref "C6") (pin "1") (pinfunction "1_1") (pintype "passive"))
      (node (ref "C61") (pin "1") (pinfunction "1_1") (pintype "passive"))
      (node (ref "C62") (pin "+") (pinfunction "+_+") (pintype "passive"))
      (node (ref "C9") (pin "1") (pinfunction "1_1") (pintype "passive"))
      (node (ref "IC3") (pin "18") (pinfunction "AVCC_18") (pintype "power_in"))
      (node (ref "IC3") (pin "4") (pinfunction "VCC_4") (pintype "power_in"))
      (node (ref "IC3") (pin "6") (pinfunction "VCC_6") (pintype "power_in"))
      (node (ref "JP1") (pin "2") (pinfunction "2_2") (pintype "passive"))
      (node (ref "LED1") (pin "1-VDD") (pinfunction "VDD_1-VDD") (pintype "power_in"))
      (node (ref "LED10") (pin "1-VDD") (pinfunction "VDD_1-VDD") (pintype "power_in"))
      (node (ref "LED11") (pin "1-VDD") (pinfunction "VDD_1-VDD") (pintype "power_in"))
      (node (ref "LED12") (pin "1-VDD") (pinfunction "VDD_1-VDD") (pintype "power_in"))
      (node (ref "LED13") (pin "1-VDD") (pinfunction "VDD_1-VDD") (pintype "power_in"))
      (node (ref "LED14") (pin "1-VDD") (pinfunction "VDD_1-VDD") (pintype "power_in"))
      (node (ref "LED15") (pin "1-VDD") (pinfunction "VDD_1-VDD") (pintype "power_in"))
      (node (ref "LED16") (pin "1-VDD") (pinfunction "VDD_1-VDD") (pintype "power_in"))
      (node (ref "LED17") (pin "1-VDD") (pinfunction "VDD_1-VDD") (pintype "power_in"))
      (node (ref "LED18") (pin "1-VDD") (pinfunction "VDD_1-VDD") (pintype "power_in"))
      (node (ref "LED19") (pin "1-VDD") (pinfunction "VDD_1-VDD") (pintype "power_in"))
      (node (ref "LED2") (pin "1-VDD") (pinfunction "VDD_1-VDD") (pintype "power_in"))
      (node (ref "LED20") (pin "1-VDD") (pinfunction "VDD_1-VDD") (pintype "power_in"))
      (node (ref "LED21") (pin "1-VDD") (pinfunction "VDD_1-VDD") (pintype "power_in"))
      (node (ref "LED22") (pin "1-VDD") (pinfunction "VDD_1-VDD") (pintype "power_in"))
      (node (ref "LED23") (pin "1-VDD") (pinfunction "VDD_1-VDD") (pintype "power_in"))
      (node (ref "LED24") (pin "1-VDD") (pinfunction "VDD_1-VDD") (pintype "power_in"))
      (node (ref "LED25") (pin "1-VDD") (pinfunction "VDD_1-VDD") (pintype "power_in"))
      (node (ref "LED26") (pin "1-VDD") (pinfunction "VDD_1-VDD") (pintype "power_in"))
      (node (ref "LED27") (pin "1-VDD") (pinfunction "VDD_1-VDD") (pintype "power_in"))
      (node (ref "LED28") (pin "1-VDD") (pinfunction "VDD_1-VDD") (pintype "power_in"))
      (node (ref "LED29") (pin "1-VDD") (pinfunction "VDD_1-VDD") (pintype "power_in"))
      (node (ref "LED3") (pin "1-VDD") (pinfunction "VDD_1-VDD") (pintype "power_in"))
      (node (ref "LED30") (pin "1-VDD") (pinfunction "VDD_1-VDD") (pintype "power_in"))
      (node (ref "LED31") (pin "1-VDD") (pinfunction "VDD_1-VDD") (pintype "power_in"))
      (node (ref "LED32") (pin "1-VDD") (pinfunction "VDD_1-VDD") (pintype "power_in"))
      (node (ref "LED33") (pin "1-VDD") (pinfunction "VDD_1-VDD") (pintype "power_in"))
      (node (ref "LED34") (pin "1-VDD") (pinfunction "VDD_1-VDD") (pintype "power_in"))
      (node (ref "LED35") (pin "1-VDD") (pinfunction "VDD_1-VDD") (pintype "power_in"))
      (node (ref "LED36") (pin "1-VDD") (pinfunction "VDD_1-VDD") (pintype "power_in"))
      (node (ref "LED37") (pin "1-VDD") (pinfunction "VDD_1-VDD") (pintype "power_in"))
      (node (ref "LED38") (pin "1-VDD") (pinfunction "VDD_1-VDD") (pintype "power_in"))
      (node (ref "LED39") (pin "1-VDD") (pinfunction "VDD_1-VDD") (pintype "power_in"))
      (node (ref "LED4") (pin "1-VDD") (pinfunction "VDD_1-VDD") (pintype "power_in"))
      (node (ref "LED40") (pin "1-VDD") (pinfunction "VDD_1-VDD") (pintype "power_in"))
      (node (ref "LED41") (pin "1-VDD") (pinfunction "VDD_1-VDD") (pintype "power_in"))
      (node (ref "LED42") (pin "1-VDD") (pinfunction "VDD_1-VDD") (pintype "power_in"))
      (node (ref "LED43") (pin "1-VDD") (pinfunction "VDD_1-VDD") (pintype "power_in"))
      (node (ref "LED44") (pin "1-VDD") (pinfunction "VDD_1-VDD") (pintype "power_in"))
      (node (ref "LED45") (pin "1-VDD") (pinfunction "VDD_1-VDD") (pintype "power_in"))
      (node (ref "LED46") (pin "1-VDD") (pinfunction "VDD_1-VDD") (pintype "power_in"))
      (node (ref "LED47") (pin "1-VDD") (pinfunction "VDD_1-VDD") (pintype "power_in"))
      (node (ref "LED48") (pin "1-VDD") (pinfunction "VDD_1-VDD") (pintype "power_in"))
      (node (ref "LED49") (pin "1-VDD") (pinfunction "VDD_1-VDD") (pintype "power_in"))
      (node (ref "LED5") (pin "1-VDD") (pinfunction "VDD_1-VDD") (pintype "power_in"))
      (node (ref "LED50") (pin "1-VDD") (pinfunction "VDD_1-VDD") (pintype "power_in"))
      (node (ref "LED6") (pin "1-VDD") (pinfunction "VDD_1-VDD") (pintype "power_in"))
      (node (ref "LED7") (pin "1-VDD") (pinfunction "VDD_1-VDD") (pintype "power_in"))
      (node (ref "LED8") (pin "1-VDD") (pinfunction "VDD_1-VDD") (pintype "power_in"))
      (node (ref "LED9") (pin "1-VDD") (pinfunction "VDD_1-VDD") (pintype "power_in"))
      (node (ref "R12") (pin "2") (pinfunction "2_2") (pintype "passive"))
      (node (ref "R15") (pin "2") (pinfunction "2_2") (pintype "passive"))
      (node (ref "R3") (pin "2") (pinfunction "2_2") (pintype "passive"))
      (node (ref "R31") (pin "2") (pinfunction "2_2") (pintype "passive"))
      (node (ref "R5") (pin "1") (pinfunction "1_1") (pintype "passive"))
      (node (ref "U1") (pin "1") (pinfunction "VOUT_1") (pintype "power_in"))
      (node (ref "U1") (pin "15") (pinfunction "VOUT_15") (pintype "power_in"))
      (node (ref "U1") (pin "16") (pinfunction "VOUT_16") (pintype "power_in"))
      (node (ref "U4") (pin "1") (pinfunction "IN_1") (pintype "power_in"))
      (node (ref "U4") (pin "3") (pinfunction "EN_3") (pintype "input"))
    )
    (net (code "2") (name "/BOOST_ENABLE") (class "Default")
      (node (ref "R13") (pin "2") (pinfunction "2_2") (pintype "passive"))
      (node (ref "U$17") (pin "P$2") (pinfunction "P$2_P$2") (pintype "bidirectional"))
      (node (ref "U1") (pin "11") (pinfunction "EN_11") (pintype "input"))
    )
    (net (code "3") (name "/CE") (class "Default")
      (node (ref "IC3") (pin "11") (pinfunction "PD7(AIN1)_11") (pintype "bidirectional"))
      (node (ref "JP3") (pin "6") (pinfunction "6_6") (pintype "passive"))
    )
    (net (code "4") (name "/CSN") (class "Default")
      (node (ref "IC3") (pin "12") (pinfunction "PB0(ICP)_12") (pintype "bidirectional"))
      (node (ref "JP3") (pin "5") (pinfunction "5_5") (pintype "passive"))
    )
    (net (code "5") (name "/LBO") (class "Default")
      (node (ref "T1") (pin "B") (pinfunction "B_B") (pintype "passive"))
      (node (ref "U1") (pin "12") (pinfunction "LBO_12") (pintype "output"))
    )
    (net (code "6") (name "/MISO") (class "Default")
      (node (ref "IC3") (pin "16") (pinfunction "PB4(MISO)_16") (pintype "bidirectional"))
      (node (ref "JP1") (pin "1") (pinfunction "1_1") (pintype "passive"))
      (node (ref "JP3") (pin "2") (pinfunction "2_2") (pintype "passive"))
    )
    (net (code "7") (name "/MOSI") (class "Default")
      (node (ref "IC3") (pin "15") (pinfunction "PB3(MOSI/OC2)_15") (pintype "bidirectional"))
      (node (ref "JP1") (pin "4") (pinfunction "4_4") (pintype "passive"))
      (node (ref "JP3") (pin "3") (pinfunction "3_3") (pintype "passive"))
    )
    (net (code "8") (name "/N$41") (class "Default")
      (node (ref "LED10") (pin "2-DOUT") (pinfunction "DO_2-DOUT") (pintype "output"))
      (node (ref "LED11") (pin "4-DIN") (pinfunction "DI_4-DIN") (pintype "input"))
    )
    (net (code "9") (name "/N$51") (class "Default")
      (node (ref "LED20") (pin "2-DOUT") (pinfunction "DO_2-DOUT") (pintype "output"))
      (node (ref "LED21") (pin "4-DIN") (pinfunction "DI_4-DIN") (pintype "input"))
    )
    (net (code "10") (name "/N$61") (class "Default")
      (node (ref "LED30") (pin "2-DOUT") (pinfunction "DO_2-DOUT") (pintype "output"))
      (node (ref "LED31") (pin "4-DIN") (pinfunction "DI_4-DIN") (pintype "input"))
    )
    (net (code "11") (name "/N$71") (class "Default")
      (node (ref "LED40") (pin "2-DOUT") (pinfunction "DO_2-DOUT") (pintype "output"))
      (node (ref "LED41") (pin "4-DIN") (pinfunction "DI_4-DIN") (pintype "input"))
    )
    (net (code "12") (name "/PIXEL_DATA") (class "Default")
      (node (ref "LED1") (pin "4-DIN") (pinfunction "DI_4-DIN") (pintype "input"))
      (node (ref "R19") (pin "2") (pinfunction "2_2") (pintype "passive"))
    )
    (net (code "13") (name "/RESET_PROG") (class "Default")
      (node (ref "IC3") (pin "29") (pinfunction "PC6(/RESET)_29") (pintype "bidirectional"))
      (node (ref "JP1") (pin "5") (pinfunction "5_5") (pintype "passive"))
      (node (ref "R31") (pin "1") (pinfunction "1_1") (pintype "passive"))
    )
    (net (code "14") (name "/RX") (class "Default")
      (node (ref "IC3") (pin "30") (pinfunction "PD0(RXD)_30") (pintype "bidirectional"))
      (node (ref "JP1") (pin "7") (pinfunction "7_7") (pintype "passive"))
    )
    (net (code "15") (name "/SCK") (class "Default")
      (node (ref "IC3") (pin "17") (pinfunction "PB5(SCK)_17") (pintype "bidirectional"))
      (node (ref "JP1") (pin "3") (pinfunction "3_3") (pintype "passive"))
      (node (ref "JP3") (pin "4") (pinfunction "4_4") (pintype "passive"))
    )
    (net (code "16") (name "/SCL") (class "Default")
      (node (ref "IC3") (pin "28") (pinfunction "PC5(ADC5/SCL)_28") (pintype "bidirectional"))
      (node (ref "Q2") (pin "3") (pinfunction "D_3") (pintype "bidirectional"))
      (node (ref "R15") (pin "1") (pinfunction "1_1") (pintype "passive"))
    )
    (net (code "17") (name "/SCL_3.3V") (class "Default")
      (node (ref "Q2") (pin "2") (pinfunction "S_2") (pintype "bidirectional"))
      (node (ref "R11") (pin "1") (pinfunction "1_1") (pintype "passive"))
      (node (ref "U3") (pin "4") (pinfunction "SCL_4") (pintype "bidirectional"))
    )
    (net (code "18") (name "/SDA") (class "Default")
      (node (ref "IC3") (pin "27") (pinfunction "PC4(ADC4/SDA)_27") (pintype "bidirectional"))
      (node (ref "Q1") (pin "3") (pinfunction "D_3") (pintype "bidirectional"))
      (node (ref "R12") (pin "1") (pinfunction "1_1") (pintype "passive"))
    )
    (net (code "19") (name "/SDA_3.3V") (class "Default")
      (node (ref "Q1") (pin "2") (pinfunction "S_2") (pintype "bidirectional"))
      (node (ref "R10") (pin "1") (pinfunction "1_1") (pintype "passive"))
      (node (ref "U3") (pin "6") (pinfunction "SDA_6") (pintype "bidirectional"))
    )
    (net (code "20") (name "/SDO") (class "Default")
      (node (ref "R18") (pin "2") (pinfunction "2_2") (pintype "passive"))
      (node (ref "U3") (pin "7") (pinfunction "SDO_7") (pintype "bidirectional"))
    )
    (net (code "21") (name "/STAT1") (class "Default")
      (node (ref "IC3") (pin "32") (pinfunction "PD2(INT0)_32") (pintype "bidirectional"))
      (node (ref "STAT1") (pin "A") (pinfunction "A_A") (pintype "passive"))
    )
    (net (code "22") (name "/STAT2") (class "Default")
      (node (ref "IC3") (pin "1") (pinfunction "PD3(INT1)_1") (pintype "bidirectional"))
      (node (ref "STAT2") (pin "A") (pinfunction "A_A") (pintype "passive"))
    )
    (net (code "23") (name "/STAT3") (class "Default")
      (node (ref "IC3") (pin "2") (pinfunction "PD4(XCK/T0)_2") (pintype "bidirectional"))
      (node (ref "STAT3") (pin "A") (pinfunction "A_A") (pintype "passive"))
    )
    (net (code "24") (name "/SW1") (class "Default")
      (node (ref "C63") (pin "1") (pinfunction "1_1") (pintype "passive"))
      (node (ref "IC3") (pin "23") (pinfunction "PC0(ADC0)_23") (pintype "bidirectional"))
      (node (ref "R24") (pin "1") (pinfunction "1_1") (pintype "passive"))
    )
    (net (code "25") (name "/SW2") (class "Default")
      (node (ref "C64") (pin "1") (pinfunction "1_1") (pintype "passive"))
      (node (ref "IC3") (pin "24") (pinfunction "PC1(ADC1)_24") (pintype "bidirectional"))
      (node (ref "R25") (pin "1") (pinfunction "1_1") (pintype "passive"))
    )
    (net (code "26") (name "/SW3") (class "Default")
      (node (ref "C65") (pin "1") (pinfunction "1_1") (pintype "passive"))
      (node (ref "IC3") (pin "25") (pinfunction "PC2(ADC2)_25") (pintype "bidirectional"))
      (node (ref "R26") (pin "1") (pinfunction "1_1") (pintype "passive"))
    )
    (net (code "27") (name "/SW4") (class "Default")
      (node (ref "C66") (pin "1") (pinfunction "1_1") (pintype "passive"))
      (node (ref "IC3") (pin "26") (pinfunction "PC3(ADC3)_26") (pintype "bidirectional"))
      (node (ref "R27") (pin "1") (pinfunction "1_1") (pintype "passive"))
    )
    (net (code "28") (name "/SW5") (class "Default")
      (node (ref "C67") (pin "1") (pinfunction "1_1") (pintype "passive"))
      (node (ref "IC3") (pin "19") (pinfunction "ADC6_19") (pintype "bidirectional"))
      (node (ref "R28") (pin "1") (pinfunction "1_1") (pintype "passive"))
    )
    (net (code "29") (name "/SW6") (class "Default")
      (node (ref "C68") (pin "1") (pinfunction "1_1") (pintype "passive"))
      (node (ref "IC3") (pin "22") (pinfunction "ADC7_22") (pintype "bidirectional"))
      (node (ref "R29") (pin "1") (pinfunction "1_1") (pintype "passive"))
    )
    (net (code "30") (name "/TX") (class "Default")
      (node (ref "IC3") (pin "31") (pinfunction "PD1(TXD)_31") (pintype "bidirectional"))
      (node (ref "JP1") (pin "8") (pinfunction "8_8") (pintype "passive"))
    )
    (net (code "31") (name "3.3V") (class "Default")
      (node (ref "C59") (pin "1") (pinfunction "1_1") (pintype "passive"))
      (node (ref "C60") (pin "1") (pinfunction "1_1") (pintype "passive"))
      (node (ref "JP3") (pin "7") (pinfunction "7_7") (pintype "passive"))
      (node (ref "Q1") (pin "1") (pinfunction "G_1") (pintype "bidirectional"))
      (node (ref "Q2") (pin "1") (pinfunction "G_1") (pintype "bidirectional"))
      (node (ref "R10") (pin "2") (pinfunction "2_2") (pintype "passive"))
      (node (ref "R11") (pin "2") (pinfunction "2_2") (pintype "passive"))
      (node (ref "R9") (pin "1") (pinfunction "1_1") (pintype "passive"))
      (node (ref "U3") (pin "1") (pinfunction "VDDIO_1") (pintype "power_in"))
      (node (ref "U3") (pin "14") (pinfunction "VDD_14") (pintype "power_in"))
      (node (ref "U4") (pin "5") (pinfunction "OUT_5") (pintype "power_in"))
    )
    (net (code "32") (name "GND") (class "Default")
      (node (ref "C1") (pin "2") (pinfunction "2_2") (pintype "passive"))
      (node (ref "C10") (pin "2") (pinfunction "2_2") (pintype "passive"))
      (node (ref "C11") (pin "2") (pinfunction "2_2") (pintype "passive"))
      (node (ref "C12") (pin "2") (pinfunction "2_2") (pintype "passive"))
      (node (ref "C13") (pin "2") (pinfunction "2_2") (pintype "passive"))
      (node (ref "C14") (pin "2") (pinfunction "2_2") (pintype "passive"))
      (node (ref "C15") (pin "2") (pinfunction "2_2") (pintype "passive"))
      (node (ref "C16") (pin "2") (pinfunction "2_2") (pintype "passive"))
      (node (ref "C17") (pin "2") (pinfunction "2_2") (pintype "passive"))
      (node (ref "C18") (pin "2") (pinfunction "2_2") (pintype "passive"))
      (node (ref "C19") (pin "2") (pinfunction "2_2") (pintype "passive"))
      (node (ref "C2") (pin "2") (pinfunction "2_2") (pintype "passive"))
      (node (ref "C20") (pin "2") (pinfunction "2_2") (pintype "passive"))
      (node (ref "C21") (pin "2") (pinfunction "2_2") (pintype "passive"))
      (node (ref "C22") (pin "2") (pinfunction "2_2") (pintype "passive"))
      (node (ref "C23") (pin "2") (pinfunction "2_2") (pintype "passive"))
      (node (ref "C24") (pin "2") (pinfunction "2_2") (pintype "passive"))
      (node (ref "C25") (pin "2") (pinfunction "2_2") (pintype "passive"))
      (node (ref "C26") (pin "2") (pinfunction "2_2") (pintype "passive"))
      (node (ref "C27") (pin "2") (pinfunction "2_2") (pintype "passive"))
      (node (ref "C28") (pin "2") (pinfunction "2_2") (pintype "passive"))
      (node (ref "C29") (pin "2") (pinfunction "2_2") (pintype "passive"))
      (node (ref "C3") (pin "2") (pinfunction "2_2") (pintype "passive"))
      (node (ref "C30") (pin "2") (pinfunction "2_2") (pintype "passive"))
      (node (ref "C31") (pin "2") (pinfunction "2_2") (pintype "passive"))
      (node (ref "C32") (pin "2") (pinfunction "2_2") (pintype "passive"))
      (node (ref "C33") (pin "2") (pinfunction "2_2") (pintype "passive"))
      (node (ref "C34") (pin "2") (pinfunction "2_2") (pintype "passive"))
      (node (ref "C35") (pin "2") (pinfunction "2_2") (pintype "passive"))
      (node (ref "C36") (pin "2") (pinfunction "2_2") (pintype "passive"))
      (node (ref "C37") (pin "2") (pinfunction "2_2") (pintype "passive"))
      (node (ref "C38") (pin "2") (pinfunction "2_2") (pintype "passive"))
      (node (ref "C39") (pin "2") (pinfunction "2_2") (pintype "passive"))
      (node (ref "C4") (pin "2") (pinfunction "2_2") (pintype "passive"))
      (node (ref "C40") (pin "2") (pinfunction "2_2") (pintype "passive"))
      (node (ref "C41") (pin "2") (pinfunction "2_2") (pintype "passive"))
      (node (ref "C42") (pin "2") (pinfunction "2_2") (pintype "passive"))
      (node (ref "C43") (pin "2") (pinfunction "2_2") (pintype "passive"))
      (node (ref "C44") (pin "2") (pinfunction "2_2") (pintype "passive"))
      (node (ref "C45") (pin "2") (pinfunction "2_2") (pintype "passive"))
      (node (ref "C46") (pin "2") (pinfunction "2_2") (pintype "passive"))
      (node (ref "C47") (pin "2") (pinfunction "2_2") (pintype "passive"))
      (node (ref "C48") (pin "2") (pinfunction "2_2") (pintype "passive"))
      (node (ref "C49") (pin "2") (pinfunction "2_2") (pintype "passive"))
      (node (ref "C5") (pin "2") (pinfunction "2_2") (pintype "passive"))
      (node (ref "C50") (pin "2") (pinfunction "2_2") (pintype "passive"))
      (node (ref "C51") (pin "2") (pinfunction "2_2") (pintype "passive"))
      (node (ref "C52") (pin "2") (pinfunction "2_2") (pintype "passive"))
      (node (ref "C53") (pin "2") (pinfunction "2_2") (pintype "passive"))
      (node (ref "C54") (pin "2") (pinfunction "2_2") (pintype "passive"))
      (node (ref "C55") (pin "2") (pinfunction "2_2") (pintype "passive"))
      (node (ref "C56") (pin "2") (pinfunction "2_2") (pintype "passive"))
      (node (ref "C57") (pin "2") (pinfunction "2_2") (pintype "passive"))
      (node (ref "C58") (pin "2") (pinfunction "2_2") (pintype "passive"))
      (node (ref "C59") (pin "2") (pinfunction "2_2") (pintype "passive"))
      (node (ref "C6") (pin "2") (pinfunction "2_2") (pintype "passive"))
      (node (ref "C60") (pin "2") (pinfunction "2_2") (pintype "passive"))
      (node (ref "C61") (pin "2") (pinfunction "2_2") (pintype "passive"))
      (node (ref "C62") (pin "-") (pinfunction "-_-") (pintype "passive"))
      (node (ref "C63") (pin "2") (pinfunction "2_2") (pintype "passive"))
      (node (ref "C64") (pin "2") (pinfunction "2_2") (pintype "passive"))
      (node (ref "C65") (pin "2") (pinfunction "2_2") (pintype "passive"))
      (node (ref "C66") (pin "2") (pinfunction "2_2") (pintype "passive"))
      (node (ref "C67") (pin "2") (pinfunction "2_2") (pintype "passive"))
      (node (ref "C68") (pin "2") (pinfunction "2_2") (pintype "passive"))
      (node (ref "C7") (pin "2") (pinfunction "2_2") (pintype "passive"))
      (node (ref "C8") (pin "2") (pinfunction "2_2") (pintype "passive"))
      (node (ref "C9") (pin "2") (pinfunction "2_2") (pintype "passive"))
      (node (ref "CN4") (pin "BASE@1") (pinfunction "GND_BASE@1") (pintype "power_in"))
      (node (ref "CN4") (pin "BASE@2") (pinfunction "GND_BASE@2") (pintype "power_in"))
      (node (ref "CN4") (pin "D+") (pinfunction "D+_D+") (pintype "bidirectional"))
      (node (ref "CN4") (pin "D-") (pinfunction "D-_D-") (pintype "bidirectional"))
      (node (ref "CN4") (pin "GND") (pinfunction "GND_GND") (pintype "power_in"))
      (node (ref "CN4") (pin "ID") (pinfunction "ID_ID") (pintype "bidirectional"))
      (node (ref "CN4") (pin "SPRT@1") (pinfunction "GND_SPRT@1") (pintype "power_in"))
      (node (ref "CN4") (pin "SPRT@2") (pinfunction "GND_SPRT@2") (pintype "power_in"))
      (node (ref "CN4") (pin "SPRT@3") (pinfunction "GND_SPRT@3") (pintype "power_in"))
      (node (ref "CN4") (pin "SPRT@4") (pinfunction "GND_SPRT@4") (pintype "power_in"))
      (node (ref "IC3") (pin "21") (pinfunction "GND_21") (pintype "power_in"))
      (node (ref "IC3") (pin "3") (pinfunction "GND_3") (pintype "power_in"))
      (node (ref "IC3") (pin "5") (pinfunction "GND_5") (pintype "power_in"))
      (node (ref "JP1") (pin "6") (pinfunction "6_6") (pintype "passive"))
      (node (ref "JP3") (pin "8") (pinfunction "8_8") (pintype "passive"))
      (node (ref "LBO") (pin "C") (pinfunction "C_C") (pintype "passive"))
      (node (ref "LED1") (pin "3-GND") (pinfunction "GND_3-GND") (pintype "power_in"))
      (node (ref "LED10") (pin "3-GND") (pinfunction "GND_3-GND") (pintype "power_in"))
      (node (ref "LED11") (pin "3-GND") (pinfunction "GND_3-GND") (pintype "power_in"))
      (node (ref "LED12") (pin "3-GND") (pinfunction "GND_3-GND") (pintype "power_in"))
      (node (ref "LED13") (pin "3-GND") (pinfunction "GND_3-GND") (pintype "power_in"))
      (node (ref "LED14") (pin "3-GND") (pinfunction "GND_3-GND") (pintype "power_in"))
      (node (ref "LED15") (pin "3-GND") (pinfunction "GND_3-GND") (pintype "power_in"))
      (node (ref "LED16") (pin "3-GND") (pinfunction "GND_3-GND") (pintype "power_in"))
      (node (ref "LED17") (pin "3-GND") (pinfunction "GND_3-GND") (pintype "power_in"))
      (node (ref "LED18") (pin "3-GND") (pinfunction "GND_3-GND") (pintype "power_in"))
      (node (ref "LED19") (pin "3-GND") (pinfunction "GND_3-GND") (pintype "power_in"))
      (node (ref "LED2") (pin "3-GND") (pinfunction "GND_3-GND") (pintype "power_in"))
      (node (ref "LED20") (pin "3-GND") (pinfunction "GND_3-GND") (pintype "power_in"))
      (node (ref "LED21") (pin "3-GND") (pinfunction "GND_3-GND") (pintype "power_in"))
      (node (ref "LED22") (pin "3-GND") (pinfunction "GND_3-GND") (pintype "power_in"))
      (node (ref "LED23") (pin "3-GND") (pinfunction "GND_3-GND") (pintype "power_in"))
      (node (ref "LED24") (pin "3-GND") (pinfunction "GND_3-GND") (pintype "power_in"))
      (node (ref "LED25") (pin "3-GND") (pinfunction "GND_3-GND") (pintype "power_in"))
      (node (ref "LED26") (pin "3-GND") (pinfunction "GND_3-GND") (pintype "power_in"))
      (node (ref "LED27") (pin "3-GND") (pinfunction "GND_3-GND") (pintype "power_in"))
      (node (ref "LED28") (pin "3-GND") (pinfunction "GND_3-GND") (pintype "power_in"))
      (node (ref "LED29") (pin "3-GND") (pinfunction "GND_3-GND") (pintype "power_in"))
      (node (ref "LED3") (pin "3-GND") (pinfunction "GND_3-GND") (pintype "power_in"))
      (node (ref "LED30") (pin "3-GND") (pinfunction "GND_3-GND") (pintype "power_in"))
      (node (ref "LED31") (pin "3-GND") (pinfunction "GND_3-GND") (pintype "power_in"))
      (node (ref "LED32") (pin "3-GND") (pinfunction "GND_3-GND") (pintype "power_in"))
      (node (ref "LED33") (pin "3-GND") (pinfunction "GND_3-GND") (pintype "power_in"))
      (node (ref "LED34") (pin "3-GND") (pinfunction "GND_3-GND") (pintype "power_in"))
      (node (ref "LED35") (pin "3-GND") (pinfunction "GND_3-GND") (pintype "power_in"))
      (node (ref "LED36") (pin "3-GND") (pinfunction "GND_3-GND") (pintype "power_in"))
      (node (ref "LED37") (pin "3-GND") (pinfunction "GND_3-GND") (pintype "power_in"))
      (node (ref "LED38") (pin "3-GND") (pinfunction "GND_3-GND") (pintype "power_in"))
      (node (ref "LED39") (pin "3-GND") (pinfunction "GND_3-GND") (pintype "power_in"))
      (node (ref "LED4") (pin "3-GND") (pinfunction "GND_3-GND") (pintype "power_in"))
      (node (ref "LED40") (pin "3-GND") (pinfunction "GND_3-GND") (pintype "power_in"))
      (node (ref "LED41") (pin "3-GND") (pinfunction "GND_3-GND") (pintype "power_in"))
      (node (ref "LED42") (pin "3-GND") (pinfunction "GND_3-GND") (pintype "power_in"))
      (node (ref "LED43") (pin "3-GND") (pinfunction "GND_3-GND") (pintype "power_in"))
      (node (ref "LED44") (pin "3-GND") (pinfunction "GND_3-GND") (pintype "power_in"))
      (node (ref "LED45") (pin "3-GND") (pinfunction "GND_3-GND") (pintype "power_in"))
      (node (ref "LED46") (pin "3-GND") (pinfunction "GND_3-GND") (pintype "power_in"))
      (node (ref "LED47") (pin "3-GND") (pinfunction "GND_3-GND") (pintype "power_in"))
      (node (ref "LED48") (pin "3-GND") (pinfunction "GND_3-GND") (pintype "power_in"))
      (node (ref "LED49") (pin "3-GND") (pinfunction "GND_3-GND") (pintype "power_in"))
      (node (ref "LED5") (pin "3-GND") (pinfunction "GND_3-GND") (pintype "power_in"))
      (node (ref "LED50") (pin "3-GND") (pinfunction "GND_3-GND") (pintype "power_in"))
      (node (ref "LED6") (pin "3-GND") (pinfunction "GND_3-GND") (pintype "power_in"))
      (node (ref "LED7") (pin "3-GND") (pinfunction "GND_3-GND") (pintype "power_in"))
      (node (ref "LED8") (pin "3-GND") (pinfunction "GND_3-GND") (pintype "power_in"))
      (node (ref "LED9") (pin "3-GND") (pinfunction "GND_3-GND") (pintype "power_in"))
      (node (ref "ON") (pin "C") (pinfunction "C_C") (pintype "passive"))
      (node (ref "R16") (pin "1") (pinfunction "1_1") (pintype "passive"))
      (node (ref "R17") (pin "1") (pinfunction "1_1") (pintype "passive"))
      (node (ref "R18") (pin "1") (pinfunction "1_1") (pintype "passive"))
      (node (ref "R2") (pin "1") (pinfunction "1_1") (pintype "passive"))
      (node (ref "R21") (pin "1") (pinfunction "1_1") (pintype "passive"))
      (node (ref "R22") (pin "1") (pinfunction "1_1") (pintype "passive"))
      (node (ref "R23") (pin "1") (pinfunction "1_1") (pintype "passive"))
      (node (ref "R4") (pin "1") (pinfunction "1_1") (pintype "passive"))
      (node (ref "R7") (pin "2") (pinfunction "2_2") (pintype "passive"))
      (node (ref "SW1") (pin "P$1") (pinfunction "P$1_P$1") (pintype "passive"))
      (node (ref "SW2") (pin "P$1") (pinfunction "P$1_P$1") (pintype "passive"))
      (node (ref "SW3") (pin "P$1") (pinfunction "P$1_P$1") (pintype "passive"))
      (node (ref "SW4") (pin "P$1") (pinfunction "P$1_P$1") (pintype "passive"))
      (node (ref "SW5") (pin "P$1") (pinfunction "P$1_P$1") (pintype "passive"))
      (node (ref "SW6") (pin "P$1") (pinfunction "P$1_P$1") (pintype "passive"))
      (node (ref "THERM") (pin "1") (pinfunction "1_1") (pintype "passive"))
      (node (ref "U$17") (pin "P$3") (pinfunction "P$3_P$3") (pintype "bidirectional"))
      (node (ref "U$22") (pin "P$4") (pinfunction "P$2_P$4") (pintype "bidirectional"))
      (node (ref "U$22") (pin "P$5") (pinfunction "P$2_P$5") (pintype "bidirectional"))
      (node (ref "U$22") (pin "P$6") (pinfunction "P$2_P$6") (pintype "bidirectional"))
      (node (ref "U1") (pin "10") (pinfunction "SYNC_10") (pintype "input"))
      (node (ref "U1") (pin "13") (pinfunction "GND_13") (pintype "power_in"))
      (node (ref "U1") (pin "5") (pinfunction "PGND_5") (pintype "power_in"))
      (node (ref "U1") (pin "6") (pinfunction "PGND_6") (pintype "power_in"))
      (node (ref "U1") (pin "7") (pinfunction "PGND_7") (pintype "power_in"))
      (node (ref "U1") (pin "P$18") (pinfunction "PGND_P$18") (pintype "power_in"))
      (node (ref "U1") (pin "P$19") (pinfunction "PGND_P$19") (pintype "power_in"))
      (node (ref "U1") (pin "P$20") (pinfunction "PGND_P$20") (pintype "power_in"))
      (node (ref "U1") (pin "P$21") (pinfunction "PGND_P$21") (pintype "power_in"))
      (node (ref "U1") (pin "P$22") (pinfunction "PGND_P$22") (pintype "power_in"))
      (node (ref "U1") (pin "THERMAL") (pinfunction "PGND_THERMAL") (pintype "power_in"))
      (node (ref "U2") (pin "P$10") (pinfunction "VSS1_P$10") (pintype "bidirectional"))
      (node (ref "U2") (pin "P$11") (pinfunction "VSS2_P$11") (pintype "bidirectional"))
      (node (ref "U2") (pin "P$21") (pinfunction "THERMAL_P$21") (pintype "bidirectional"))
      (node (ref "U3") (pin "10") (pinfunction "RES(GND)_10") (pintype "bidirectional"))
      (node (ref "U3") (pin "12") (pinfunction "GND_12") (pintype "power_in"))
      (node (ref "U3") (pin "5") (pinfunction "GND_5") (pintype "power_in"))
      (node (ref "U4") (pin "2") (pinfunction "GND_2") (pintype "power_in"))
    )
    (net (code "33") (name "Net-(CHRG/LBO-PadC)") (class "Default")
      (node (ref "CHRG/LBO") (pin "C") (pinfunction "C_C") (pintype "passive"))
      (node (ref "R8") (pin "2") (pinfunction "2_2") (pintype "passive"))
    )
    (net (code "34") (name "Net-(DONE-PadC)") (class "Default")
      (node (ref "DONE") (pin "C") (pinfunction "C_C") (pintype "passive"))
      (node (ref "R14") (pin "2") (pinfunction "2_2") (pintype "passive"))
    )
    (net (code "35") (name "Net-(IC3-PB6(XTAL1{slash}TOSC1))") (class "Default")
      (node (ref "C5") (pin "1") (pinfunction "1_1") (pintype "passive"))
      (node (ref "IC3") (pin "7") (pinfunction "PB6(XTAL1/TOSC1)_7") (pintype "bidirectional"))
      (node (ref "Y1") (pin "3") (pinfunction "2_3") (pintype "passive"))
    )
    (net (code "36") (name "Net-(IC3-PB7(XTAL2{slash}TOSC2))") (class "Default")
      (node (ref "C3") (pin "1") (pinfunction "1_1") (pintype "passive"))
      (node (ref "IC3") (pin "8") (pinfunction "PB7(XTAL2/TOSC2)_8") (pintype "bidirectional"))
      (node (ref "Y1") (pin "1") (pinfunction "1_1") (pintype "passive"))
    )
    (net (code "37") (name "Net-(IC3-PD6(AIN0))") (class "Default")
      (node (ref "IC3") (pin "10") (pinfunction "PD6(AIN0)_10") (pintype "bidirectional"))
      (node (ref "R19") (pin "1") (pinfunction "1_1") (pintype "passive"))
    )
    (net (code "38") (name "Net-(L1-2)") (class "Default")
      (node (ref "L1") (pin "P$2") (pinfunction "2_P$2") (pintype "passive"))
      (node (ref "U1") (pin "3") (pinfunction "SW_3") (pintype "input"))
      (node (ref "U1") (pin "4") (pinfunction "SW_4") (pintype "input"))
    )
    (net (code "39") (name "Net-(LBO-PadA)") (class "Default")
      (node (ref "LBO") (pin "A") (pinfunction "A_A") (pintype "passive"))
      (node (ref "R20") (pin "1") (pinfunction "1_1") (pintype "passive"))
    )
    (net (code "40") (name "Net-(LED1-DO)") (class "Default")
      (node (ref "LED1") (pin "2-DOUT") (pinfunction "DO_2-DOUT") (pintype "output"))
      (node (ref "LED2") (pin "4-DIN") (pinfunction "DI_4-DIN") (pintype "input"))
    )
    (net (code "41") (name "Net-(LED2-DO)") (class "Default")
      (node (ref "LED2") (pin "2-DOUT") (pinfunction "DO_2-DOUT") (pintype "output"))
      (node (ref "LED3") (pin "4-DIN") (pinfunction "DI_4-DIN") (pintype "input"))
    )
    (net (code "42") (name "Net-(LED3-DO)") (class "Default")
      (node (ref "LED3") (pin "2-DOUT") (pinfunction "DO_2-DOUT") (pintype "output"))
      (node (ref "LED4") (pin "4-DIN") (pinfunction "DI_4-DIN") (pintype "input"))
    )
    (net (code "43") (name "Net-(LED4-DO)") (class "Default")
      (node (ref "LED4") (pin "2-DOUT") (pinfunction "DO_2-DOUT") (pintype "output"))
      (node (ref "LED5") (pin "4-DIN") (pinfunction "DI_4-DIN") (pintype "input"))
    )
    (net (code "44") (name "Net-(LED5-DO)") (class "Default")
      (node (ref "LED5") (pin "2-DOUT") (pinfunction "DO_2-DOUT") (pintype "output"))
      (node (ref "LED6") (pin "4-DIN") (pinfunction "DI_4-DIN") (pintype "input"))
    )
    (net (code "45") (name "Net-(LED6-DO)") (class "Default")
      (node (ref "LED6") (pin "2-DOUT") (pinfunction "DO_2-DOUT") (pintype "output"))
      (node (ref "LED7") (pin "4-DIN") (pinfunction "DI_4-DIN") (pintype "input"))
    )
    (net (code "46") (name "Net-(LED7-DO)") (class "Default")
      (node (ref "LED7") (pin "2-DOUT") (pinfunction "DO_2-DOUT") (pintype "output"))
      (node (ref "LED8") (pin "4-DIN") (pinfunction "DI_4-DIN") (pintype "input"))
    )
    (net (code "47") (name "Net-(LED8-DO)") (class "Default")
      (node (ref "LED8") (pin "2-DOUT") (pinfunction "DO_2-DOUT") (pintype "output"))
      (node (ref "LED9") (pin "4-DIN") (pinfunction "DI_4-DIN") (pintype "input"))
    )
    (net (code "48") (name "Net-(LED10-DI)") (class "Default")
      (node (ref "LED10") (pin "4-DIN") (pinfunction "DI_4-DIN") (pintype "input"))
      (node (ref "LED9") (pin "2-DOUT") (pinfunction "DO_2-DOUT") (pintype "output"))
    )
    (net (code "49") (name "Net-(LED11-DO)") (class "Default")
      (node (ref "LED11") (pin "2-DOUT") (pinfunction "DO_2-DOUT") (pintype "output"))
      (node (ref "LED12") (pin "4-DIN") (pinfunction "DI_4-DIN") (pintype "input"))
    )
    (net (code "50") (name "Net-(LED12-DO)") (class "Default")
      (node (ref "LED12") (pin "2-DOUT") (pinfunction "DO_2-DOUT") (pintype "output"))
      (node (ref "LED13") (pin "4-DIN") (pinfunction "DI_4-DIN") (pintype "input"))
    )
    (net (code "51") (name "Net-(LED13-DO)") (class "Default")
      (node (ref "LED13") (pin "2-DOUT") (pinfunction "DO_2-DOUT") (pintype "output"))
      (node (ref "LED14") (pin "4-DIN") (pinfunction "DI_4-DIN") (pintype "input"))
    )
    (net (code "52") (name "Net-(LED14-DO)") (class "Default")
      (node (ref "LED14") (pin "2-DOUT") (pinfunction "DO_2-DOUT") (pintype "output"))
      (node (ref "LED15") (pin "4-DIN") (pinfunction "DI_4-DIN") (pintype "input"))
    )
    (net (code "53") (name "Net-(LED15-DO)") (class "Default")
      (node (ref "LED15") (pin "2-DOUT") (pinfunction "DO_2-DOUT") (pintype "output"))
      (node (ref "LED16") (pin "4-DIN") (pinfunction "DI_4-DIN") (pintype "input"))
    )
    (net (code "54") (name "Net-(LED16-DO)") (class "Default")
      (node (ref "LED16") (pin "2-DOUT") (pinfunction "DO_2-DOUT") (pintype "output"))
      (node (ref "LED17") (pin "4-DIN") (pinfunction "DI_4-DIN") (pintype "input"))
    )
    (net (code "55") (name "Net-(LED17-DO)") (class "Default")
      (node (ref "LED17") (pin "2-DOUT") (pinfunction "DO_2-DOUT") (pintype "output"))
      (node (ref "LED18") (pin "4-DIN") (pinfunction "DI_4-DIN") (pintype "input"))
    )
    (net (code "56") (name "Net-(LED18-DO)") (class "Default")
      (node (ref "LED18") (pin "2-DOUT") (pinfunction "DO_2-DOUT") (pintype "output"))
      (node (ref "LED19") (pin "4-DIN") (pinfunction "DI_4-DIN") (pintype "input"))
    )
    (net (code "57") (name "Net-(LED19-DO)") (class "Default")
      (node (ref "LED19") (pin "2-DOUT") (pinfunction "DO_2-DOUT") (pintype "output"))
      (node (ref "LED20") (pin "4-DIN") (pinfunction "DI_4-DIN") (pintype "input"))
    )
    (net (code "58") (name "Net-(LED21-DO)") (class "Default")
      (node (ref "LED21") (pin "2-DOUT") (pinfunction "DO_2-DOUT") (pintype "output"))
      (node (ref "LED22") (pin "4-DIN") (pinfunction "DI_4-DIN") (pintype "input"))
    )
    (net (code "59") (name "Net-(LED22-DO)") (class "Default")
      (node (ref "LED22") (pin "2-DOUT") (pinfunction "DO_2-DOUT") (pintype "output"))
      (node (ref "LED23") (pin "4-DIN") (pinfunction "DI_4-DIN") (pintype "input"))
    )
    (net (code "60") (name "Net-(LED23-DO)") (class "Default")
      (node (ref "LED23") (pin "2-DOUT") (pinfunction "DO_2-DOUT") (pintype "output"))
      (node (ref "LED24") (pin "4-DIN") (pinfunction "DI_4-DIN") (pintype "input"))
    )
    (net (code "61") (name "Net-(LED24-DO)") (class "Default")
      (node (ref "LED24") (pin "2-DOUT") (pinfunction "DO_2-DOUT") (pintype "output"))
      (node (ref "LED25") (pin "4-DIN") (pinfunction "DI_4-DIN") (pintype "input"))
    )
    (net (code "62") (name "Net-(LED25-DO)") (class "Default")
      (node (ref "LED25") (pin "2-DOUT") (pinfunction "DO_2-DOUT") (pintype "output"))
      (node (ref "LED26") (pin "4-DIN") (pinfunction "DI_4-DIN") (pintype "input"))
    )
    (net (code "63") (name "Net-(LED26-DO)") (class "Default")
      (node (ref "LED26") (pin "2-DOUT") (pinfunction "DO_2-DOUT") (pintype "output"))
      (node (ref "LED27") (pin "4-DIN") (pinfunction "DI_4-DIN") (pintype "input"))
    )
    (net (code "64") (name "Net-(LED27-DO)") (class "Default")
      (node (ref "LED27") (pin "2-DOUT") (pinfunction "DO_2-DOUT") (pintype "output"))
      (node (ref "LED28") (pin "4-DIN") (pinfunction "DI_4-DIN") (pintype "input"))
    )
    (net (code "65") (name "Net-(LED28-DO)") (class "Default")
      (node (ref "LED28") (pin "2-DOUT") (pinfunction "DO_2-DOUT") (pintype "output"))
      (node (ref "LED29") (pin "4-DIN") (pinfunction "DI_4-DIN") (pintype "input"))
    )
    (net (code "66") (name "Net-(LED29-DO)") (class "Default")
      (node (ref "LED29") (pin "2-DOUT") (pinfunction "DO_2-DOUT") (pintype "output"))
      (node (ref "LED30") (pin "4-DIN") (pinfunction "DI_4-DIN") (pintype "input"))
    )
    (net (code "67") (name "Net-(LED31-DO)") (class "Default")
      (node (ref "LED31") (pin "2-DOUT") (pinfunction "DO_2-DOUT") (pintype "output"))
      (node (ref "LED32") (pin "4-DIN") (pinfunction "DI_4-DIN") (pintype "input"))
    )
    (net (code "68") (name "Net-(LED32-DO)") (class "Default")
      (node (ref "LED32") (pin "2-DOUT") (pinfunction "DO_2-DOUT") (pintype "output"))
      (node (ref "LED33") (pin "4-DIN") (pinfunction "DI_4-DIN") (pintype "input"))
    )
    (net (code "69") (name "Net-(LED33-DO)") (class "Default")
      (node (ref "LED33") (pin "2-DOUT") (pinfunction "DO_2-DOUT") (pintype "output"))
      (node (ref "LED34") (pin "4-DIN") (pinfunction "DI_4-DIN") (pintype "input"))
    )
    (net (code "70") (name "Net-(LED34-DO)") (class "Default")
      (node (ref "LED34") (pin "2-DOUT") (pinfunction "DO_2-DOUT") (pintype "output"))
      (node (ref "LED35") (pin "4-DIN") (pinfunction "DI_4-DIN") (pintype "input"))
    )
    (net (code "71") (name "Net-(LED35-DO)") (class "Default")
      (node (ref "LED35") (pin "2-DOUT") (pinfunction "DO_2-DOUT") (pintype "output"))
      (node (ref "LED36") (pin "4-DIN") (pinfunction "DI_4-DIN") (pintype "input"))
    )
    (net (code "72") (name "Net-(LED36-DO)") (class "Default")
      (node (ref "LED36") (pin "2-DOUT") (pinfunction "DO_2-DOUT") (pintype "output"))
      (node (ref "LED37") (pin "4-DIN") (pinfunction "DI_4-DIN") (pintype "input"))
    )
    (net (code "73") (name "Net-(LED37-DO)") (class "Default")
      (node (ref "LED37") (pin "2-DOUT") (pinfunction "DO_2-DOUT") (pintype "output"))
      (node (ref "LED38") (pin "4-DIN") (pinfunction "DI_4-DIN") (pintype "input"))
    )
    (net (code "74") (name "Net-(LED38-DO)") (class "Default")
      (node (ref "LED38") (pin "2-DOUT") (pinfunction "DO_2-DOUT") (pintype "output"))
      (node (ref "LED39") (pin "4-DIN") (pinfunction "DI_4-DIN") (pintype "input"))
    )
    (net (code "75") (name "Net-(LED39-DO)") (class "Default")
      (node (ref "LED39") (pin "2-DOUT") (pinfunction "DO_2-DOUT") (pintype "output"))
      (node (ref "LED40") (pin "4-DIN") (pinfunction "DI_4-DIN") (pintype "input"))
    )
    (net (code "76") (name "Net-(LED41-DO)") (class "Default")
      (node (ref "LED41") (pin "2-DOUT") (pinfunction "DO_2-DOUT") (pintype "output"))
      (node (ref "LED42") (pin "4-DIN") (pinfunction "DI_4-DIN") (pintype "input"))
    )
    (net (code "77") (name "Net-(LED42-DO)") (class "Default")
      (node (ref "LED42") (pin "2-DOUT") (pinfunction "DO_2-DOUT") (pintype "output"))
      (node (ref "LED43") (pin "4-DIN") (pinfunction "DI_4-DIN") (pintype "input"))
    )
    (net (code "78") (name "Net-(LED43-DO)") (class "Default")
      (node (ref "LED43") (pin "2-DOUT") (pinfunction "DO_2-DOUT") (pintype "output"))
      (node (ref "LED44") (pin "4-DIN") (pinfunction "DI_4-DIN") (pintype "input"))
    )
    (net (code "79") (name "Net-(LED44-DO)") (class "Default")
      (node (ref "LED44") (pin "2-DOUT") (pinfunction "DO_2-DOUT") (pintype "output"))
      (node (ref "LED45") (pin "4-DIN") (pinfunction "DI_4-DIN") (pintype "input"))
    )
    (net (code "80") (name "Net-(LED45-DO)") (class "Default")
      (node (ref "LED45") (pin "2-DOUT") (pinfunction "DO_2-DOUT") (pintype "output"))
      (node (ref "LED46") (pin "4-DIN") (pinfunction "DI_4-DIN") (pintype "input"))
    )
    (net (code "81") (name "Net-(LED46-DO)") (class "Default")
      (node (ref "LED46") (pin "2-DOUT") (pinfunction "DO_2-DOUT") (pintype "output"))
      (node (ref "LED47") (pin "4-DIN") (pinfunction "DI_4-DIN") (pintype "input"))
    )
    (net (code "82") (name "Net-(LED47-DO)") (class "Default")
      (node (ref "LED47") (pin "2-DOUT") (pinfunction "DO_2-DOUT") (pintype "output"))
      (node (ref "LED48") (pin "4-DIN") (pinfunction "DI_4-DIN") (pintype "input"))
    )
    (net (code "83") (name "Net-(LED48-DO)") (class "Default")
      (node (ref "LED48") (pin "2-DOUT") (pinfunction "DO_2-DOUT") (pintype "output"))
      (node (ref "LED49") (pin "4-DIN") (pinfunction "DI_4-DIN") (pintype "input"))
    )
    (net (code "84") (name "Net-(LED49-DO)") (class "Default")
      (node (ref "LED49") (pin "2-DOUT") (pinfunction "DO_2-DOUT") (pintype "output"))
      (node (ref "LED50") (pin "4-DIN") (pinfunction "DI_4-DIN") (pintype "input"))
    )
    (net (code "85") (name "Net-(ON-PadA)") (class "Default")
      (node (ref "ON") (pin "A") (pinfunction "A_A") (pintype "passive"))
      (node (ref "R5") (pin "2") (pinfunction "2_2") (pintype "passive"))
    )
    (net (code "86") (name "Net-(R20-Pad2)") (class "Default")
      (node (ref "R20") (pin "2") (pinfunction "2_2") (pintype "passive"))
      (node (ref "T1") (pin "C") (pinfunction "C_C") (pintype "passive"))
    )
    (net (code "87") (name "Net-(R21-Pad2)") (class "Default")
      (node (ref "R21") (pin "2") (pinfunction "2_2") (pintype "passive"))
      (node (ref "STAT2") (pin "C") (pinfunction "C_C") (pintype "passive"))
    )
    (net (code "88") (name "Net-(R22-Pad2)") (class "Default")
      (node (ref "R22") (pin "2") (pinfunction "2_2") (pintype "passive"))
      (node (ref "STAT3") (pin "C") (pinfunction "C_C") (pintype "passive"))
    )
    (net (code "89") (name "Net-(R23-Pad2)") (class "Default")
      (node (ref "R23") (pin "2") (pinfunction "2_2") (pintype "passive"))
      (node (ref "STAT1") (pin "C") (pinfunction "C_C") (pintype "passive"))
    )
    (net (code "90") (name "Net-(R24-Pad2)") (class "Default")
      (node (ref "R24") (pin "2") (pinfunction "2_2") (pintype "passive"))
      (node (ref "SW1") (pin "P$2") (pinfunction "P$2_P$2") (pintype "passive"))
    )
    (net (code "91") (name "Net-(R25-Pad2)") (class "Default")
      (node (ref "R25") (pin "2") (pinfunction "2_2") (pintype "passive"))
      (node (ref "SW2") (pin "P$2") (pinfunction "P$2_P$2") (pintype "passive"))
    )
    (net (code "92") (name "Net-(R26-Pad2)") (class "Default")
      (node (ref "R26") (pin "2") (pinfunction "2_2") (pintype "passive"))
      (node (ref "SW3") (pin "P$2") (pinfunction "P$2_P$2") (pintype "passive"))
    )
    (net (code "93") (name "Net-(R27-Pad2)") (class "Default")
      (node (ref "R27") (pin "2") (pinfunction "2_2") (pintype "passive"))
      (node (ref "SW4") (pin "P$2") (pinfunction "P$2_P$2") (pintype "passive"))
    )
    (net (code "94") (name "Net-(R28-Pad2)") (class "Default")
      (node (ref "R28") (pin "2") (pinfunction "2_2") (pintype "passive"))
      (node (ref "SW5") (pin "P$2") (pinfunction "P$2_P$2") (pintype "passive"))
    )
    (net (code "95") (name "Net-(R29-Pad2)") (class "Default")
      (node (ref "R29") (pin "2") (pinfunction "2_2") (pintype "passive"))
      (node (ref "SW6") (pin "P$2") (pinfunction "P$2_P$2") (pintype "passive"))
    )
    (net (code "96") (name "Net-(U1-FB)") (class "Default")
      (node (ref "R3") (pin "1") (pinfunction "1_1") (pintype "passive"))
      (node (ref "R4") (pin "2") (pinfunction "2_2") (pintype "passive"))
      (node (ref "U1") (pin "14") (pinfunction "FB_14") (pintype "input"))
    )
    (net (code "97") (name "Net-(U1-LBI)") (class "Default")
      (node (ref "R1") (pin "1") (pinfunction "1_1") (pintype "passive"))
      (node (ref "R2") (pin "2") (pinfunction "2_2") (pintype "passive"))
      (node (ref "U1") (pin "9") (pinfunction "LBI_9") (pintype "input"))
    )
    (net (code "98") (name "Net-(U2-PROG1)") (class "Default")
      (node (ref "R16") (pin "2") (pinfunction "2_2") (pintype "passive"))
      (node (ref "U2") (pin "P$13") (pinfunction "PROG1_P$13") (pintype "bidirectional"))
    )
    (net (code "99") (name "Net-(U2-PROG3)") (class "Default")
      (node (ref "R17") (pin "2") (pinfunction "2_2") (pintype "passive"))
      (node (ref "U2") (pin "P$12") (pinfunction "PROG3_P$12") (pintype "bidirectional"))
    )
    (net (code "100") (name "Net-(U2-STAT1{slash}LBO)") (class "Default")
      (node (ref "R8") (pin "1") (pinfunction "1_1") (pintype "passive"))
      (node (ref "U2") (pin "P$8") (pinfunction "STAT1/LBO_P$8") (pintype "bidirectional"))
    )
    (net (code "101") (name "Net-(U2-STAT2)") (class "Default")
      (node (ref "R14") (pin "1") (pinfunction "1_1") (pintype "passive"))
      (node (ref "U2") (pin "P$7") (pinfunction "STAT2_P$7") (pintype "bidirectional"))
    )
    (net (code "102") (name "Net-(U2-THERM)") (class "Default")
      (node (ref "THERM") (pin "2") (pinfunction "2_2") (pintype "passive"))
      (node (ref "U2") (pin "P$5") (pinfunction "THERM_P$5") (pintype "bidirectional"))
    )
    (net (code "103") (name "Net-(U2-VPCC)") (class "Default")
      (node (ref "R6") (pin "1") (pinfunction "1_1") (pintype "passive"))
      (node (ref "R7") (pin "1") (pinfunction "1_1") (pintype "passive"))
      (node (ref "U2") (pin "P$2") (pinfunction "VPCC_P$2") (pintype "bidirectional"))
    )
    (net (code "104") (name "Net-(U3-CS)") (class "Default")
      (node (ref "R9") (pin "2") (pinfunction "2_2") (pintype "passive"))
      (node (ref "U3") (pin "8") (pinfunction "CS_8") (pintype "input"))
    )
    (net (code "105") (name "VBAT") (class "Default")
      (node (ref "C1") (pin "1") (pinfunction "1_1") (pintype "passive"))
      (node (ref "C4") (pin "1") (pinfunction "1_1") (pintype "passive"))
      (node (ref "L1") (pin "P$1") (pinfunction "1_P$1") (pintype "passive"))
      (node (ref "R1") (pin "2") (pinfunction "2_2") (pintype "passive"))
      (node (ref "R13") (pin "1") (pinfunction "1_1") (pintype "passive"))
      (node (ref "T1") (pin "E") (pinfunction "E_E") (pintype "passive"))
      (node (ref "U1") (pin "8") (pinfunction "VBAT_8") (pintype "input"))
      (node (ref "U2") (pin "P$1") (pinfunction "VOUT1_P$1") (pintype "bidirectional"))
      (node (ref "U2") (pin "P$20") (pinfunction "VOUT2_P$20") (pintype "bidirectional"))
    )
    (net (code "106") (name "VBUS") (class "Default")
      (node (ref "C8") (pin "1") (pinfunction "1_1") (pintype "passive"))
      (node (ref "CHRG/LBO") (pin "A") (pinfunction "A_A") (pintype "passive"))
      (node (ref "CN4") (pin "VBUS") (pinfunction "VBUS_VBUS") (pintype "power_in"))
      (node (ref "DONE") (pin "A") (pinfunction "A_A") (pintype "passive"))
      (node (ref "R6") (pin "2") (pinfunction "2_2") (pintype "passive"))
      (node (ref "U2") (pin "P$17") (pinfunction "CE_P$17") (pintype "bidirectional"))
      (node (ref "U2") (pin "P$18") (pinfunction "VIN1_P$18") (pintype "bidirectional"))
      (node (ref "U2") (pin "P$19") (pinfunction "VIN2_P$19") (pintype "bidirectional"))
      (node (ref "U2") (pin "P$3") (pinfunction "SEL_P$3") (pintype "bidirectional"))
      (node (ref "U2") (pin "P$4") (pinfunction "PROG2_P$4") (pintype "bidirectional"))
      (node (ref "U2") (pin "P$9") (pinfunction "/TE_P$9") (pintype "bidirectional"))
    )
    (net (code "107") (name "VLIPO") (class "Default")
      (node (ref "C7") (pin "1") (pinfunction "1_1") (pintype "passive"))
      (node (ref "U$22") (pin "P$1") (pinfunction "P$1_P$1") (pintype "bidirectional"))
      (node (ref "U$22") (pin "P$2") (pinfunction "P$1_P$2") (pintype "bidirectional"))
      (node (ref "U$22") (pin "P$3") (pinfunction "P$1_P$3") (pintype "bidirectional"))
      (node (ref "U2") (pin "P$14") (pinfunction "VBAT1_P$14") (pintype "bidirectional"))
      (node (ref "U2") (pin "P$15") (pinfunction "VBAT2_P$15") (pintype "bidirectional"))
      (node (ref "U2") (pin "P$16") (pinfunction "VBATSENS_P$16") (pintype "bidirectional"))
    )
    (net (code "108") (name "unconnected-(IC3-AREF-Pad20)") (class "Default")
      (node (ref "IC3") (pin "20") (pinfunction "AREF_20") (pintype "passive"))
    )
    (net (code "109") (name "unconnected-(IC3-PB1(OC1A)-Pad13)") (class "Default")
      (node (ref "IC3") (pin "13") (pinfunction "PB1(OC1A)_13") (pintype "bidirectional"))
    )
    (net (code "110") (name "unconnected-(IC3-PB2(SS{slash}OC1B)-Pad14)") (class "Default")
      (node (ref "IC3") (pin "14") (pinfunction "PB2(SS/OC1B)_14") (pintype "bidirectional"))
    )
    (net (code "111") (name "unconnected-(IC3-PD5(T1)-Pad9)") (class "Default")
      (node (ref "IC3") (pin "9") (pinfunction "PD5(T1)_9") (pintype "bidirectional"))
    )
    (net (code "112") (name "unconnected-(JP3-Pad1)") (class "Default")
      (node (ref "JP3") (pin "1") (pinfunction "1_1") (pintype "passive"))
    )
    (net (code "113") (name "unconnected-(LED50-DO-Pad2-DOUT)") (class "Default")
      (node (ref "LED50") (pin "2-DOUT") (pinfunction "DO_2-DOUT") (pintype "output"))
    )
    (net (code "114") (name "unconnected-(U$17-PadP$1)") (class "Default")
      (node (ref "U$17") (pin "P$1") (pinfunction "P$1_P$1") (pintype "bidirectional"))
    )
    (net (code "115") (name "unconnected-(U2-{slash}PG-PadP$6)") (class "Default")
      (node (ref "U2") (pin "P$6") (pinfunction "/PG_P$6") (pintype "bidirectional"))
    )
    (net (code "116") (name "unconnected-(U3-ADC1-Pad16)") (class "Default")
      (node (ref "U3") (pin "16") (pinfunction "ADC1_16") (pintype "input"))
    )
    (net (code "117") (name "unconnected-(U3-ADC2-Pad15)") (class "Default")
      (node (ref "U3") (pin "15") (pinfunction "ADC2_15") (pintype "input"))
    )
    (net (code "118") (name "unconnected-(U3-ADC3-Pad13)") (class "Default")
      (node (ref "U3") (pin "13") (pinfunction "ADC3_13") (pintype "input"))
    )
    (net (code "119") (name "unconnected-(U3-INT1-Pad11)") (class "Default")
      (node (ref "U3") (pin "11") (pinfunction "INT1_11") (pintype "output"))
    )
    (net (code "120") (name "unconnected-(U3-INT2-Pad9)") (class "Default")
      (node (ref "U3") (pin "9") (pinfunction "INT2_9") (pintype "output"))
    )
    (net (code "121") (name "unconnected-(U3-NC-Pad2)") (class "Default")
      (node (ref "U3") (pin "2") (pinfunction "NC_2") (pintype "no_connect"))
    )
    (net (code "122") (name "unconnected-(U3-NC-Pad3)") (class "Default")
      (node (ref "U3") (pin "3") (pinfunction "NC_3") (pintype "no_connect"))
    )
    (net (code "123") (name "unconnected-(U4-P4-Pad4)") (class "Default")
      (node (ref "U4") (pin "4") (pinfunction "P4_4") (pintype "bidirectional"))
    )
  )
)
